# ESP32S3_DevBoard.net
KiCad netlist of a schematic drawn in EAGLE
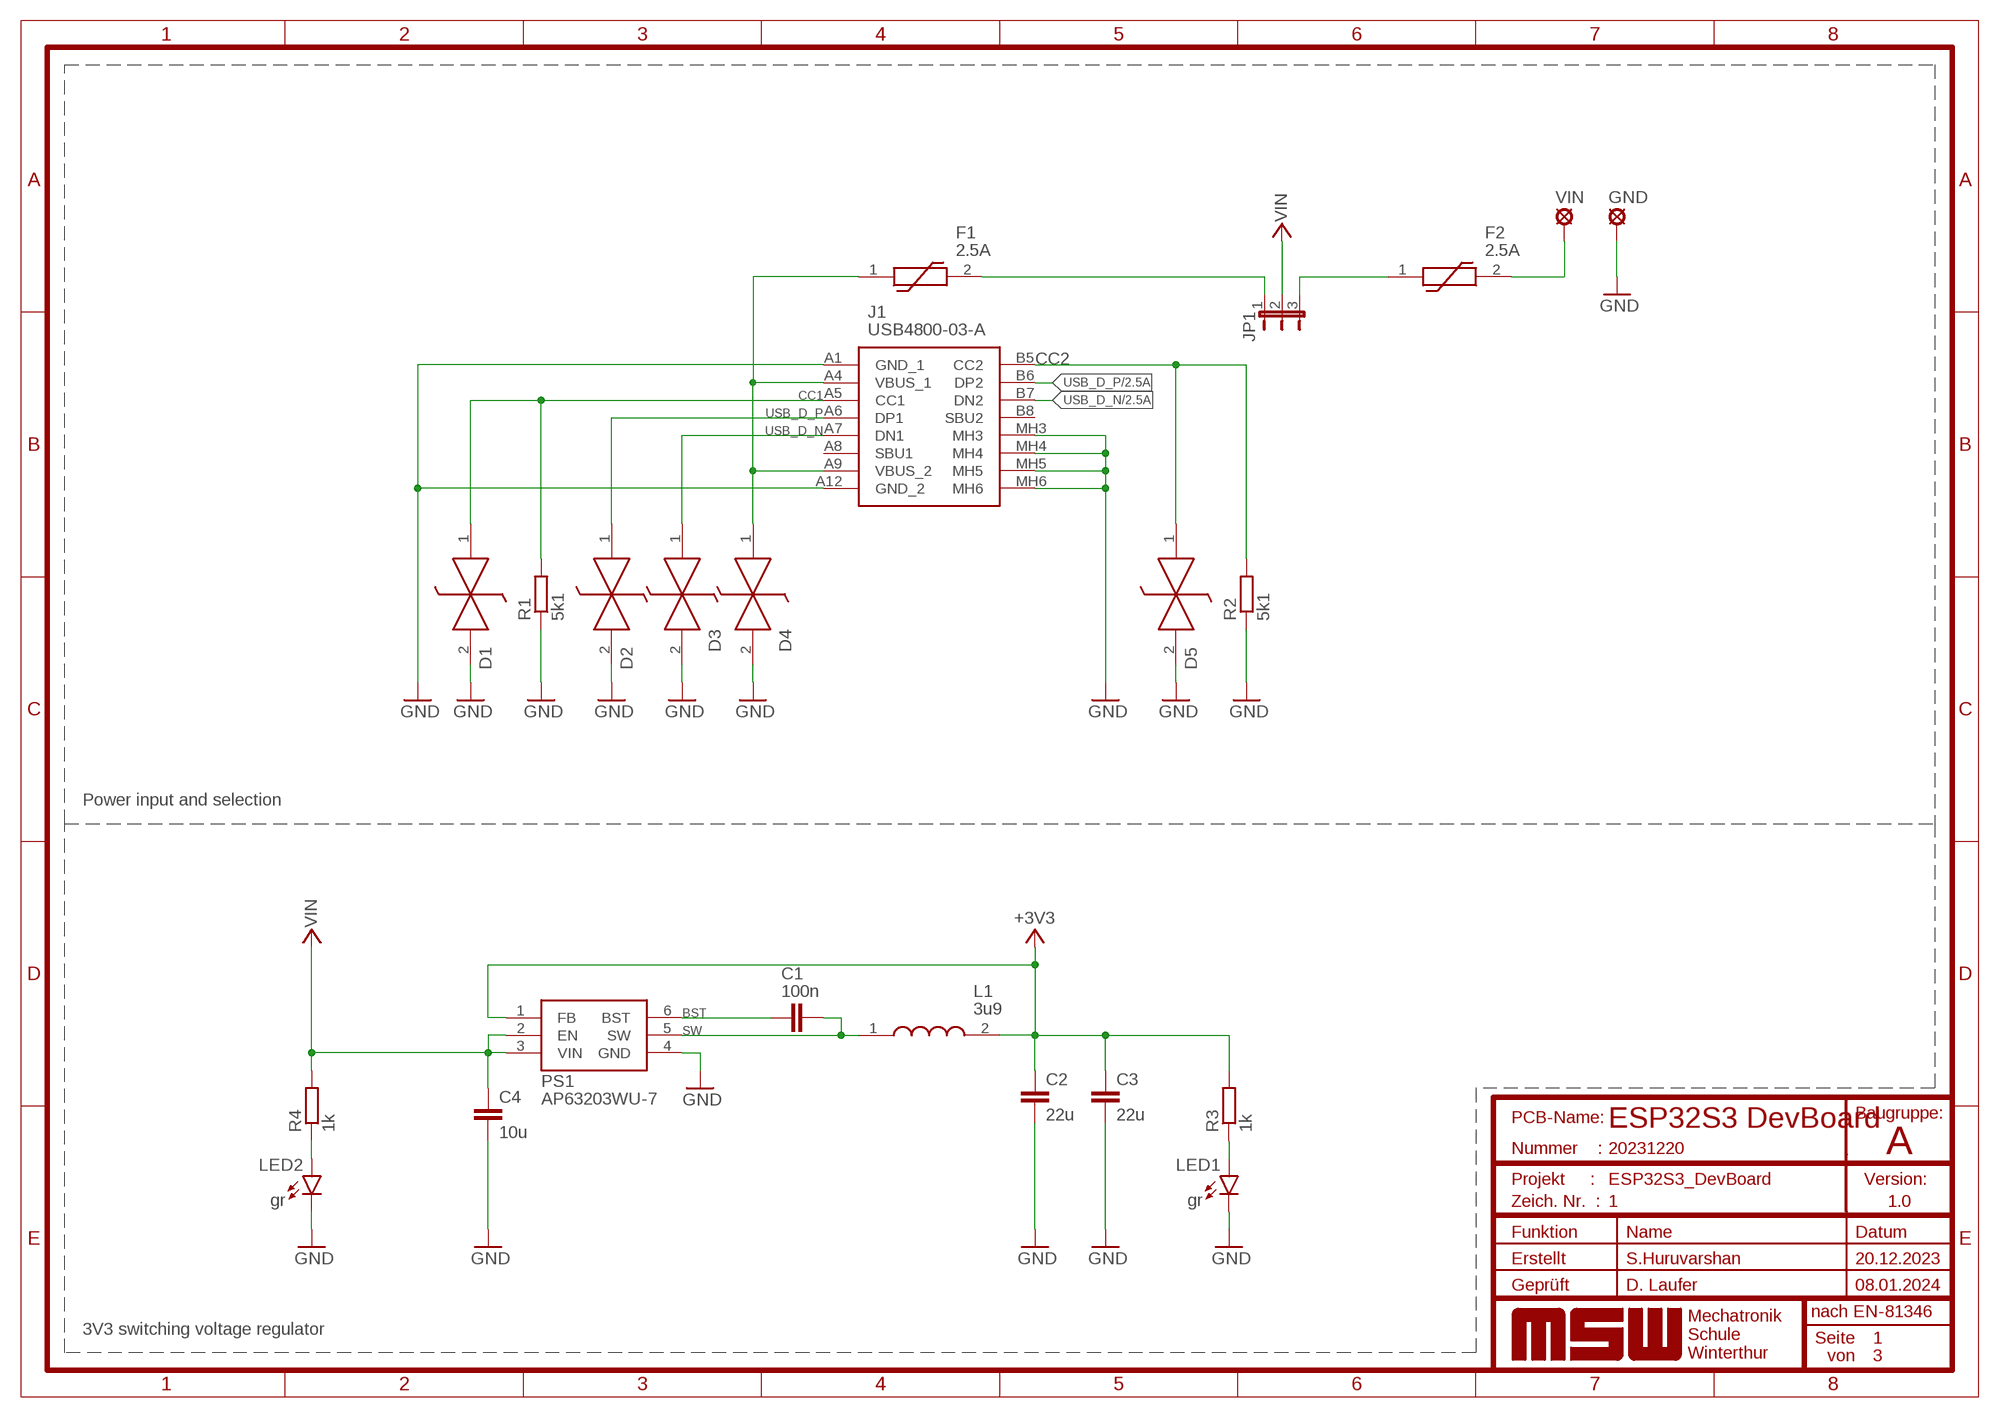
[diagram p0: schematic, sheet 1]
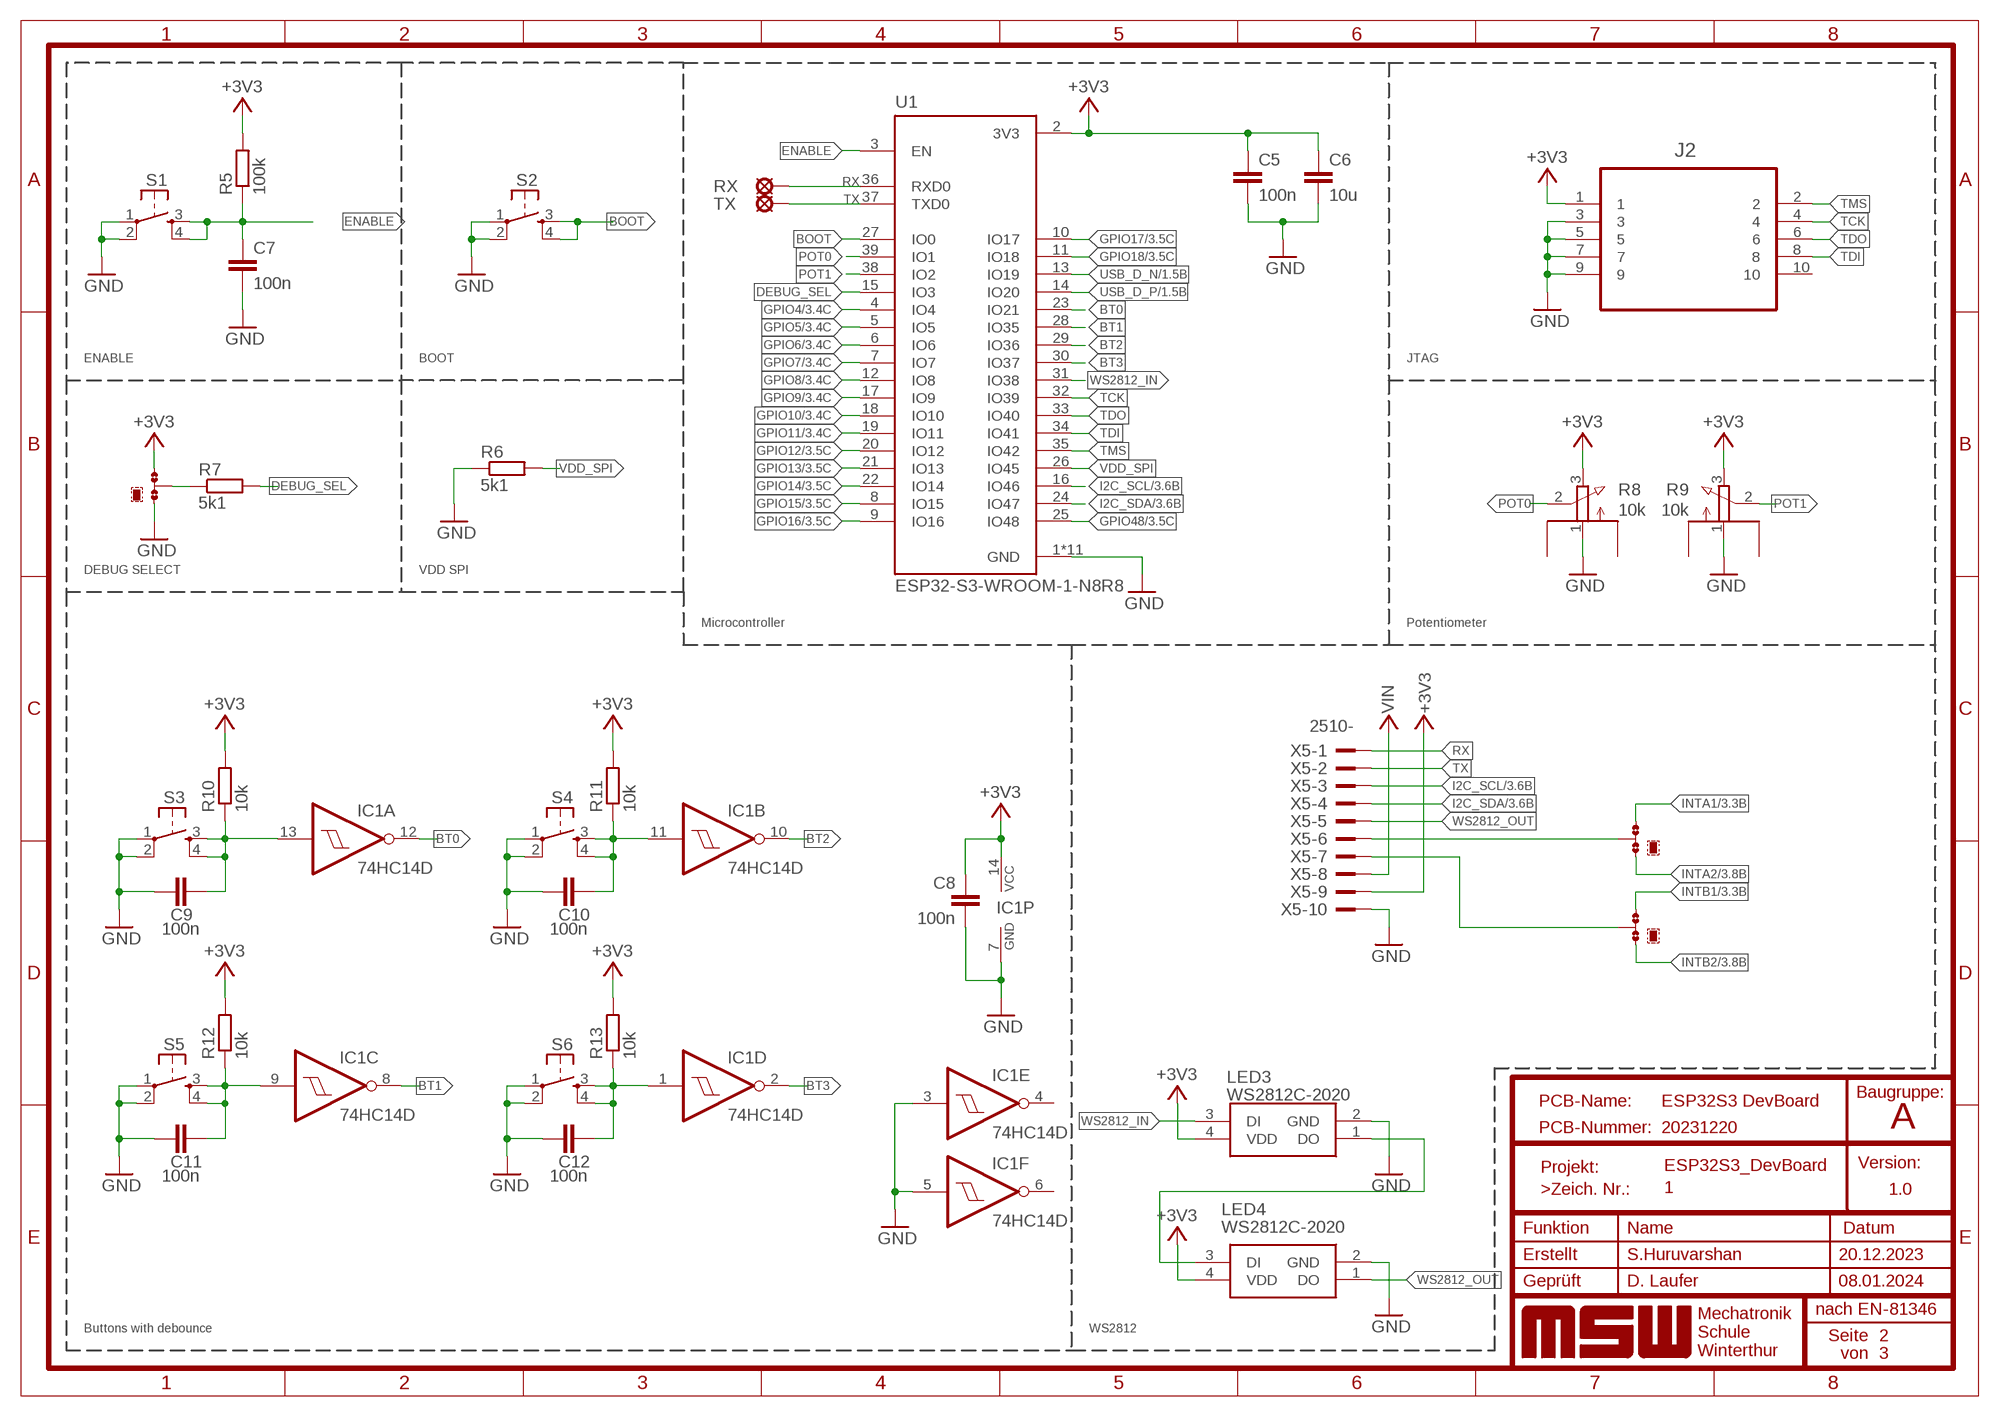
[diagram p1: schematic, sheet 2]
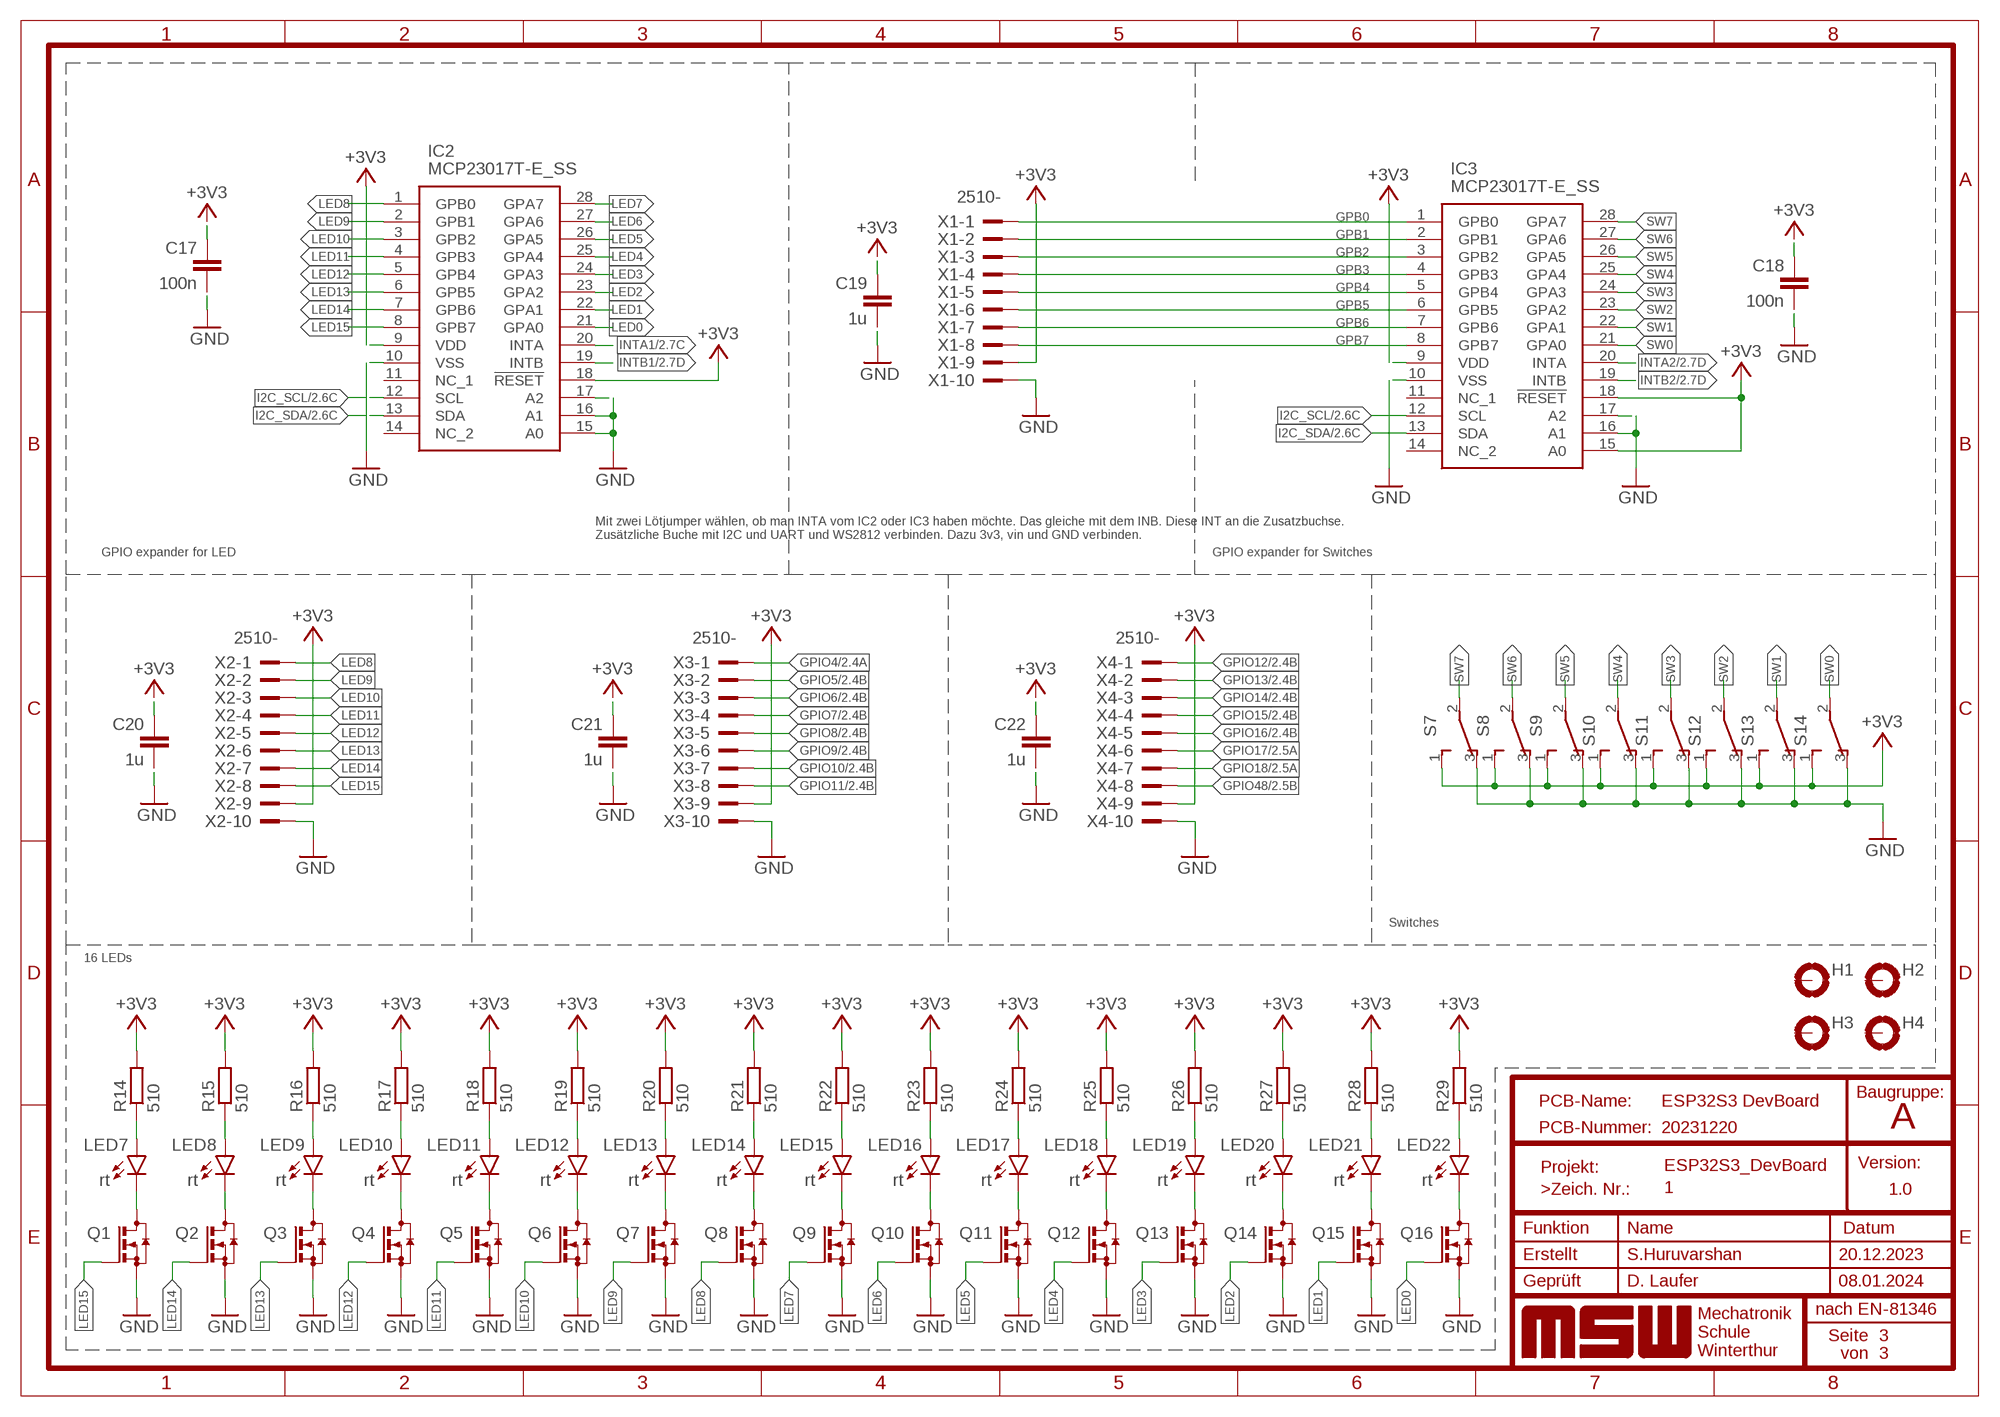
[diagram p2: schematic, sheet 3]

(export (version "E")
  (design (tool "Eeschema 10.0.6"))
  (components
    (comp (ref "C17")
      (value "100n")
      (footprint "eagle-import:C0805")
      (libsource (lib "eagle-import") (part "C-EUC0805"))
    )
    (comp (ref "C18")
      (value "100n")
      (footprint "eagle-import:C0805")
      (libsource (lib "eagle-import") (part "C-EUC0805"))
    )
    (comp (ref "C19")
      (value "1u")
      (footprint "eagle-import:C0805")
      (libsource (lib "eagle-import") (part "C-EUC0805"))
    )
    (comp (ref "C20")
      (value "1u")
      (footprint "eagle-import:C0805")
      (libsource (lib "eagle-import") (part "C-EUC0805"))
    )
    (comp (ref "C21")
      (value "1u")
      (footprint "eagle-import:C0805")
      (libsource (lib "eagle-import") (part "C-EUC0805"))
    )
    (comp (ref "C22")
      (value "1u")
      (footprint "eagle-import:C0805")
      (libsource (lib "eagle-import") (part "C-EUC0805"))
    )
    (comp (ref "H1")
      (value "MOUNT-PAD-ROUND3.3")
      (footprint "eagle-import:3,3-PAD")
      (libsource (lib "eagle-import") (part "MOUNT-PAD-ROUND3.3"))
    )
    (comp (ref "H2")
      (value "MOUNT-PAD-ROUND3.3")
      (footprint "eagle-import:3,3-PAD")
      (libsource (lib "eagle-import") (part "MOUNT-PAD-ROUND3.3"))
    )
    (comp (ref "H3")
      (value "MOUNT-PAD-ROUND3.3")
      (footprint "eagle-import:3,3-PAD")
      (libsource (lib "eagle-import") (part "MOUNT-PAD-ROUND3.3"))
    )
    (comp (ref "H4")
      (value "MOUNT-PAD-ROUND3.3")
      (footprint "eagle-import:3,3-PAD")
      (libsource (lib "eagle-import") (part "MOUNT-PAD-ROUND3.3"))
    )
    (comp (ref "IC2")
      (value "MCP23017T-E_SS")
      (footprint "eagle-import:SOP65P780X200-28N")
      (fields
        (field (name "MANUFACTURER_PART_NUMBER") "MCP23017T-E/SS")
        (field (name "MOUSER_PART_NUMBER") "579-MCP23017T-E/SS")
      )
      (libsource (lib "eagle-import") (part "MCP23017T-E_SS"))
    )
    (comp (ref "IC3")
      (value "MCP23017T-E_SS")
      (footprint "eagle-import:SOP65P780X200-28N")
      (fields
        (field (name "MANUFACTURER_PART_NUMBER") "MCP23017T-E/SS")
        (field (name "MOUSER_PART_NUMBER") "579-MCP23017T-E/SS")
      )
      (libsource (lib "eagle-import") (part "MCP23017T-E_SS"))
    )
    (comp (ref "LED7")
      (value "rt")
      (footprint "eagle-import:CHIPLED_1206")
      (libsource (lib "eagle-import") (part "LEDCHIPLED_1206"))
    )
    (comp (ref "LED8")
      (value "rt")
      (footprint "eagle-import:CHIPLED_1206")
      (libsource (lib "eagle-import") (part "LEDCHIPLED_1206"))
    )
    (comp (ref "LED9")
      (value "rt")
      (footprint "eagle-import:CHIPLED_1206")
      (libsource (lib "eagle-import") (part "LEDCHIPLED_1206"))
    )
    (comp (ref "LED10")
      (value "rt")
      (footprint "eagle-import:CHIPLED_1206")
      (libsource (lib "eagle-import") (part "LEDCHIPLED_1206"))
    )
    (comp (ref "LED11")
      (value "rt")
      (footprint "eagle-import:CHIPLED_1206")
      (libsource (lib "eagle-import") (part "LEDCHIPLED_1206"))
    )
    (comp (ref "LED12")
      (value "rt")
      (footprint "eagle-import:CHIPLED_1206")
      (libsource (lib "eagle-import") (part "LEDCHIPLED_1206"))
    )
    (comp (ref "LED13")
      (value "rt")
      (footprint "eagle-import:CHIPLED_1206")
      (libsource (lib "eagle-import") (part "LEDCHIPLED_1206"))
    )
    (comp (ref "LED14")
      (value "rt")
      (footprint "eagle-import:CHIPLED_1206")
      (libsource (lib "eagle-import") (part "LEDCHIPLED_1206"))
    )
    (comp (ref "LED15")
      (value "rt")
      (footprint "eagle-import:CHIPLED_1206")
      (libsource (lib "eagle-import") (part "LEDCHIPLED_1206"))
    )
    (comp (ref "LED16")
      (value "rt")
      (footprint "eagle-import:CHIPLED_1206")
      (libsource (lib "eagle-import") (part "LEDCHIPLED_1206"))
    )
    (comp (ref "LED17")
      (value "rt")
      (footprint "eagle-import:CHIPLED_1206")
      (libsource (lib "eagle-import") (part "LEDCHIPLED_1206"))
    )
    (comp (ref "LED18")
      (value "rt")
      (footprint "eagle-import:CHIPLED_1206")
      (libsource (lib "eagle-import") (part "LEDCHIPLED_1206"))
    )
    (comp (ref "LED19")
      (value "rt")
      (footprint "eagle-import:CHIPLED_1206")
      (libsource (lib "eagle-import") (part "LEDCHIPLED_1206"))
    )
    (comp (ref "LED20")
      (value "rt")
      (footprint "eagle-import:CHIPLED_1206")
      (libsource (lib "eagle-import") (part "LEDCHIPLED_1206"))
    )
    (comp (ref "LED21")
      (value "rt")
      (footprint "eagle-import:CHIPLED_1206")
      (libsource (lib "eagle-import") (part "LEDCHIPLED_1206"))
    )
    (comp (ref "LED22")
      (value "rt")
      (footprint "eagle-import:CHIPLED_1206")
      (libsource (lib "eagle-import") (part "LEDCHIPLED_1206"))
    )
    (comp (ref "Q1")
      (value "PMV20EN")
      (footprint "eagle-import:SOT23")
      (libsource (lib "eagle-import") (part "BSS123"))
    )
    (comp (ref "Q2")
      (value "PMV20EN")
      (footprint "eagle-import:SOT23")
      (libsource (lib "eagle-import") (part "BSS123"))
    )
    (comp (ref "Q3")
      (value "PMV20EN")
      (footprint "eagle-import:SOT23")
      (libsource (lib "eagle-import") (part "BSS123"))
    )
    (comp (ref "Q4")
      (value "PMV20EN")
      (footprint "eagle-import:SOT23")
      (libsource (lib "eagle-import") (part "BSS123"))
    )
    (comp (ref "Q5")
      (value "PMV20EN")
      (footprint "eagle-import:SOT23")
      (libsource (lib "eagle-import") (part "BSS123"))
    )
    (comp (ref "Q6")
      (value "PMV20EN")
      (footprint "eagle-import:SOT23")
      (libsource (lib "eagle-import") (part "BSS123"))
    )
    (comp (ref "Q7")
      (value "PMV20EN")
      (footprint "eagle-import:SOT23")
      (libsource (lib "eagle-import") (part "BSS123"))
    )
    (comp (ref "Q8")
      (value "PMV20EN")
      (footprint "eagle-import:SOT23")
      (libsource (lib "eagle-import") (part "BSS123"))
    )
    (comp (ref "Q9")
      (value "PMV20EN")
      (footprint "eagle-import:SOT23")
      (libsource (lib "eagle-import") (part "BSS123"))
    )
    (comp (ref "Q10")
      (value "PMV20EN")
      (footprint "eagle-import:SOT23")
      (libsource (lib "eagle-import") (part "BSS123"))
    )
    (comp (ref "Q11")
      (value "PMV20EN")
      (footprint "eagle-import:SOT23")
      (libsource (lib "eagle-import") (part "BSS123"))
    )
    (comp (ref "Q12")
      (value "PMV20EN")
      (footprint "eagle-import:SOT23")
      (libsource (lib "eagle-import") (part "BSS123"))
    )
    (comp (ref "Q13")
      (value "PMV20EN")
      (footprint "eagle-import:SOT23")
      (libsource (lib "eagle-import") (part "BSS123"))
    )
    (comp (ref "Q14")
      (value "PMV20EN")
      (footprint "eagle-import:SOT23")
      (libsource (lib "eagle-import") (part "BSS123"))
    )
    (comp (ref "Q15")
      (value "PMV20EN")
      (footprint "eagle-import:SOT23")
      (libsource (lib "eagle-import") (part "BSS123"))
    )
    (comp (ref "Q16")
      (value "PMV20EN")
      (footprint "eagle-import:SOT23")
      (libsource (lib "eagle-import") (part "BSS123"))
    )
    (comp (ref "R14")
      (value "510")
      (footprint "eagle-import:R0805")
      (libsource (lib "eagle-import") (part "R-EU_R0805"))
    )
    (comp (ref "R15")
      (value "510")
      (footprint "eagle-import:R0805")
      (libsource (lib "eagle-import") (part "R-EU_R0805"))
    )
    (comp (ref "R16")
      (value "510")
      (footprint "eagle-import:R0805")
      (libsource (lib "eagle-import") (part "R-EU_R0805"))
    )
    (comp (ref "R17")
      (value "510")
      (footprint "eagle-import:R0805")
      (libsource (lib "eagle-import") (part "R-EU_R0805"))
    )
    (comp (ref "R18")
      (value "510")
      (footprint "eagle-import:R0805")
      (libsource (lib "eagle-import") (part "R-EU_R0805"))
    )
    (comp (ref "R19")
      (value "510")
      (footprint "eagle-import:R0805")
      (libsource (lib "eagle-import") (part "R-EU_R0805"))
    )
    (comp (ref "R20")
      (value "510")
      (footprint "eagle-import:R0805")
      (libsource (lib "eagle-import") (part "R-EU_R0805"))
    )
    (comp (ref "R21")
      (value "510")
      (footprint "eagle-import:R0805")
      (libsource (lib "eagle-import") (part "R-EU_R0805"))
    )
    (comp (ref "R22")
      (value "510")
      (footprint "eagle-import:R0805")
      (libsource (lib "eagle-import") (part "R-EU_R0805"))
    )
    (comp (ref "R23")
      (value "510")
      (footprint "eagle-import:R0805")
      (libsource (lib "eagle-import") (part "R-EU_R0805"))
    )
    (comp (ref "R24")
      (value "510")
      (footprint "eagle-import:R0805")
      (libsource (lib "eagle-import") (part "R-EU_R0805"))
    )
    (comp (ref "R25")
      (value "510")
      (footprint "eagle-import:R0805")
      (libsource (lib "eagle-import") (part "R-EU_R0805"))
    )
    (comp (ref "R26")
      (value "510")
      (footprint "eagle-import:R0805")
      (libsource (lib "eagle-import") (part "R-EU_R0805"))
    )
    (comp (ref "R27")
      (value "510")
      (footprint "eagle-import:R0805")
      (libsource (lib "eagle-import") (part "R-EU_R0805"))
    )
    (comp (ref "R28")
      (value "510")
      (footprint "eagle-import:R0805")
      (libsource (lib "eagle-import") (part "R-EU_R0805"))
    )
    (comp (ref "R29")
      (value "510")
      (footprint "eagle-import:R0805")
      (libsource (lib "eagle-import") (part "R-EU_R0805"))
    )
    (comp (ref "S7")
      (value "TL36POSPDT_5MM")
      (footprint "eagle-import:SPDT_5MM")
      (libsource (lib "eagle-import") (part "TL36POSPDT_5MM"))
    )
    (comp (ref "S8")
      (value "TL36POSPDT_5MM")
      (footprint "eagle-import:SPDT_5MM")
      (libsource (lib "eagle-import") (part "TL36POSPDT_5MM"))
    )
    (comp (ref "S9")
      (value "TL36POSPDT_5MM")
      (footprint "eagle-import:SPDT_5MM")
      (libsource (lib "eagle-import") (part "TL36POSPDT_5MM"))
    )
    (comp (ref "S10")
      (value "TL36POSPDT_5MM")
      (footprint "eagle-import:SPDT_5MM")
      (libsource (lib "eagle-import") (part "TL36POSPDT_5MM"))
    )
    (comp (ref "S11")
      (value "TL36POSPDT_5MM")
      (footprint "eagle-import:SPDT_5MM")
      (libsource (lib "eagle-import") (part "TL36POSPDT_5MM"))
    )
    (comp (ref "S12")
      (value "TL36POSPDT_5MM")
      (footprint "eagle-import:SPDT_5MM")
      (libsource (lib "eagle-import") (part "TL36POSPDT_5MM"))
    )
    (comp (ref "S13")
      (value "TL36POSPDT_5MM")
      (footprint "eagle-import:SPDT_5MM")
      (libsource (lib "eagle-import") (part "TL36POSPDT_5MM"))
    )
    (comp (ref "S14")
      (value "TL36POSPDT_5MM")
      (footprint "eagle-import:SPDT_5MM")
      (libsource (lib "eagle-import") (part "TL36POSPDT_5MM"))
    )
    (comp (ref "X1")
      (value "2510-")
      (footprint "eagle-import:PAK100_2500-10")
      (fields (field (name "MF") "3M") (field (name "MPN") "2510-6002UB"))
      (libsource (lib "eagle-import") (part "2510-"))
    )
    (comp (ref "X2")
      (value "2510-")
      (footprint "eagle-import:PAK100_2500-10")
      (fields (field (name "MF") "3M") (field (name "MPN") "2510-6002UB"))
      (libsource (lib "eagle-import") (part "2510-"))
    )
    (comp (ref "X3")
      (value "2510-")
      (footprint "eagle-import:PAK100_2500-10")
      (fields (field (name "MF") "3M") (field (name "MPN") "2510-6002UB"))
      (libsource (lib "eagle-import") (part "2510-"))
    )
    (comp (ref "X4")
      (value "2510-")
      (footprint "eagle-import:PAK100_2500-10")
      (fields (field (name "MF") "3M") (field (name "MPN") "2510-6002UB"))
      (libsource (lib "eagle-import") (part "2510-"))
    )
    (comp (ref "C1")
      (value "100n")
      (footprint "eagle-import:C0805")
      (libsource (lib "eagle-import") (part "C-EUC0805"))
    )
    (comp (ref "C2")
      (value "22u")
      (footprint "eagle-import:C1206")
      (libsource (lib "eagle-import") (part "C-EUC1206"))
    )
    (comp (ref "C3")
      (value "22u")
      (footprint "eagle-import:C1206")
      (libsource (lib "eagle-import") (part "C-EUC1206"))
    )
    (comp (ref "C4")
      (value "10u")
      (footprint "eagle-import:C1206")
      (libsource (lib "eagle-import") (part "C-EUC1206"))
    )
    (comp (ref "D1")
      (value "GG060305100N2P")
      (footprint "eagle-import:DIONC1608X70N")
      (fields (field (name "MOUSER_PART_NUMBER") "581-GG060305100N2P"))
      (libsource (lib "eagle-import") (part "GG060305100N2P"))
    )
    (comp (ref "D2")
      (value "GG060305100N2P")
      (footprint "eagle-import:DIONC1608X70N")
      (fields (field (name "MOUSER_PART_NUMBER") "581-GG060305100N2P"))
      (libsource (lib "eagle-import") (part "GG060305100N2P"))
    )
    (comp (ref "D3")
      (value "GG060305100N2P")
      (footprint "eagle-import:DIONC1608X70N")
      (fields (field (name "MOUSER_PART_NUMBER") "581-GG060305100N2P"))
      (libsource (lib "eagle-import") (part "GG060305100N2P"))
    )
    (comp (ref "D4")
      (value "GG060305100N2P")
      (footprint "eagle-import:DIONC1608X70N")
      (fields (field (name "MOUSER_PART_NUMBER") "581-GG060305100N2P"))
      (libsource (lib "eagle-import") (part "GG060305100N2P"))
    )
    (comp (ref "D5")
      (value "GG060305100N2P")
      (footprint "eagle-import:DIONC1608X70N")
      (fields (field (name "MOUSER_PART_NUMBER") "581-GG060305100N2P"))
      (libsource (lib "eagle-import") (part "GG060305100N2P"))
    )
    (comp (ref "F1")
      (value "2.5A")
      (footprint "eagle-import:2920L030DR")
      (fields
        (field (name "MANUFACTURER_PART_NUMBER") "2920L250DR")
        (field (name "MOUSER_PART_NUMBER") "576-2920L250")
      )
      (libsource (lib "eagle-import") (part "2920L250DR"))
    )
    (comp (ref "F2")
      (value "2.5A")
      (footprint "eagle-import:2920L030DR")
      (fields
        (field (name "MANUFACTURER_PART_NUMBER") "2920L250DR")
        (field (name "MOUSER_PART_NUMBER") "576-2920L250")
      )
      (libsource (lib "eagle-import") (part "2920L250DR"))
    )
    (comp (ref "GND")
      (value "LSP10")
      (footprint "eagle-import:LSP10")
      (libsource (lib "eagle-import") (part "LSP10"))
    )
    (comp (ref "J1")
      (value "USB4800-03-A")
      (footprint "eagle-import:USB480003A")
      (fields (field (name "MOUSER_PART_NUMBER") "640-USB4800-03-A"))
      (libsource (lib "eagle-import") (part "USB4800-03-A"))
    )
    (comp (ref "JP1")
      (value "JP2W")
      (footprint "eagle-import:JP2W")
      (libsource (lib "eagle-import") (part "JP2W"))
    )
    (comp (ref "L1")
      (value "3u9")
      (footprint "eagle-import:74404052039")
      (fields
        (field (name "MANUFACTURER_PART_NUMBER") "74404052039")
        (field (name "MOUSER_PART_NUMBER") "710-74404052039")
      )
      (libsource (lib "eagle-import") (part "74404052039"))
    )
    (comp (ref "LED1")
      (value "gr")
      (footprint "eagle-import:CHIPLED_1206")
      (libsource (lib "eagle-import") (part "LEDCHIPLED_1206"))
    )
    (comp (ref "LED2")
      (value "gr")
      (footprint "eagle-import:CHIPLED_1206")
      (libsource (lib "eagle-import") (part "LEDCHIPLED_1206"))
    )
    (comp (ref "PS1")
      (value "AP63203WU-7")
      (footprint "eagle-import:SOT95P280X100-6N")
      (fields (field (name "MOUSER_PART_NUMBER") "621-AP63203WU-7"))
      (libsource (lib "eagle-import") (part "AP63203WU-7"))
    )
    (comp (ref "R1")
      (value "5k1")
      (footprint "eagle-import:R0805")
      (libsource (lib "eagle-import") (part "R-EU_R0805"))
    )
    (comp (ref "R2")
      (value "5k1")
      (footprint "eagle-import:R0805")
      (libsource (lib "eagle-import") (part "R-EU_R0805"))
    )
    (comp (ref "R3")
      (value "1k")
      (footprint "eagle-import:R0805")
      (libsource (lib "eagle-import") (part "R-EU_R0805"))
    )
    (comp (ref "R4")
      (value "1k")
      (footprint "eagle-import:R0805")
      (libsource (lib "eagle-import") (part "R-EU_R0805"))
    )
    (comp (ref "VIN")
      (value "LSP10")
      (footprint "eagle-import:LSP10")
      (libsource (lib "eagle-import") (part "LSP10"))
    )
    (comp (ref "C5")
      (value "100n")
      (footprint "eagle-import:C0805")
      (libsource (lib "eagle-import") (part "C-EUC0805"))
    )
    (comp (ref "C6")
      (value "10u")
      (footprint "eagle-import:C1206")
      (libsource (lib "eagle-import") (part "C-EUC1206"))
    )
    (comp (ref "C7")
      (value "100n")
      (footprint "eagle-import:C0805")
      (libsource (lib "eagle-import") (part "C-EUC0805"))
    )
    (comp (ref "C8")
      (value "100n")
      (footprint "eagle-import:C0805")
      (libsource (lib "eagle-import") (part "C-EUC0805"))
    )
    (comp (ref "C9")
      (value "100n")
      (footprint "eagle-import:C0805")
      (libsource (lib "eagle-import") (part "C-EUC0805"))
    )
    (comp (ref "C10")
      (value "100n")
      (footprint "eagle-import:C0805")
      (libsource (lib "eagle-import") (part "C-EUC0805"))
    )
    (comp (ref "C11")
      (value "100n")
      (footprint "eagle-import:C0805")
      (libsource (lib "eagle-import") (part "C-EUC0805"))
    )
    (comp (ref "C12")
      (value "100n")
      (footprint "eagle-import:C0805")
      (libsource (lib "eagle-import") (part "C-EUC0805"))
    )
    (comp (ref "IC1")
      (value "74HC14D")
      (footprint "eagle-import:SO14")
      (libsource (lib "eagle-import") (part "7414DHC"))
    )
    (comp (ref "J2")
      (value "3220-10-0100-00")
      (footprint "eagle-import:SAMTEC_FTS-105-01-L-D")
      (fields (field (name "MPN") "FTS-105-01-L-D"))
      (libsource (lib "eagle-import") (part "FTS-105-01-L-D"))
    )
    (comp (ref "JMP1")
      (value "0R-JUMPC")
      (footprint "eagle-import:C0R-JMP")
      (libsource (lib "eagle-import") (part "0R-JUMPC"))
    )
    (comp (ref "JMP2")
      (value "0R-JUMPC")
      (footprint "eagle-import:C0R-JMP")
      (libsource (lib "eagle-import") (part "0R-JUMPC"))
    )
    (comp (ref "JMP3")
      (value "0R-JUMPC")
      (footprint "eagle-import:C0R-JMP")
      (libsource (lib "eagle-import") (part "0R-JUMPC"))
    )
    (comp (ref "LED3")
      (value "WS2812C-2020")
      (footprint "eagle-import:WS2812C2020")
      (libsource (lib "eagle-import") (part "WS2812C-2020"))
    )
    (comp (ref "LED4")
      (value "WS2812C-2020")
      (footprint "eagle-import:WS2812C2020")
      (libsource (lib "eagle-import") (part "WS2812C-2020"))
    )
    (comp (ref "R5")
      (value "100k")
      (footprint "eagle-import:R0805")
      (libsource (lib "eagle-import") (part "R-EU_R0805"))
    )
    (comp (ref "R6")
      (value "5k1")
      (footprint "eagle-import:R0805")
      (libsource (lib "eagle-import") (part "R-EU_R0805"))
    )
    (comp (ref "R7")
      (value "5k1")
      (footprint "eagle-import:R0805")
      (libsource (lib "eagle-import") (part "R-EU_R0805"))
    )
    (comp (ref "R8")
      (value "10k")
      (footprint "eagle-import:EVUF")
      (libsource (lib "eagle-import") (part "EVUA"))
    )
    (comp (ref "R9")
      (value "10k")
      (footprint "eagle-import:EVUF")
      (libsource (lib "eagle-import") (part "EVUA"))
    )
    (comp (ref "R10")
      (value "10k")
      (footprint "eagle-import:R0805")
      (libsource (lib "eagle-import") (part "R-EU_R0805"))
    )
    (comp (ref "R11")
      (value "10k")
      (footprint "eagle-import:R0805")
      (libsource (lib "eagle-import") (part "R-EU_R0805"))
    )
    (comp (ref "R12")
      (value "10k")
      (footprint "eagle-import:R0805")
      (libsource (lib "eagle-import") (part "R-EU_R0805"))
    )
    (comp (ref "R13")
      (value "10k")
      (footprint "eagle-import:R0805")
      (libsource (lib "eagle-import") (part "R-EU_R0805"))
    )
    (comp (ref "RX")
      (value "LSP10")
      (footprint "eagle-import:LSP10")
      (libsource (lib "eagle-import") (part "LSP10"))
    )
    (comp (ref "S1")
      (value "TS42_4PAD")
      (footprint "eagle-import:TS42_4PAD")
      (libsource (lib "eagle-import") (part "TS42_4PAD"))
    )
    (comp (ref "S2")
      (value "TS42_4PAD")
      (footprint "eagle-import:TS42_4PAD")
      (libsource (lib "eagle-import") (part "TS42_4PAD"))
    )
    (comp (ref "S3")
      (value "TS42_4PAD")
      (footprint "eagle-import:TS42_4PAD")
      (libsource (lib "eagle-import") (part "TS42_4PAD"))
    )
    (comp (ref "S4")
      (value "TS42_4PAD")
      (footprint "eagle-import:TS42_4PAD")
      (libsource (lib "eagle-import") (part "TS42_4PAD"))
    )
    (comp (ref "S5")
      (value "TS42_4PAD")
      (footprint "eagle-import:TS42_4PAD")
      (libsource (lib "eagle-import") (part "TS42_4PAD"))
    )
    (comp (ref "S6")
      (value "TS42_4PAD")
      (footprint "eagle-import:TS42_4PAD")
      (libsource (lib "eagle-import") (part "TS42_4PAD"))
    )
    (comp (ref "TX")
      (value "LSP10")
      (footprint "eagle-import:LSP10")
      (libsource (lib "eagle-import") (part "LSP10"))
    )
    (comp (ref "U1")
      (value "ESP32-S3-WROOM-1-N8R8")
      (footprint "eagle-import:XCVR_ESP32S3WROOM1N8R8")
      (fields (field (name "MF") "Espressif Systems"))
      (libsource (lib "eagle-import") (part "ESP32-S3-WROOM-1-N8R8"))
    )
    (comp (ref "X5")
      (value "2510-")
      (footprint "eagle-import:PAK100_2500-10")
      (fields (field (name "MF") "3M") (field (name "MPN") "2510-6002UB"))
      (libsource (lib "eagle-import") (part "2510-"))
    )
  )
  (nets
    (net (code "1") (name "+3V3") (class "Default")
      (node (ref "C17") (pin "1") (pinfunction "1_1") (pintype "passive"))
      (node (ref "C18") (pin "1") (pinfunction "1_1") (pintype "passive"))
      (node (ref "C19") (pin "1") (pinfunction "1_1") (pintype "passive"))
      (node (ref "C2") (pin "1") (pinfunction "1_1") (pintype "passive"))
      (node (ref "C20") (pin "1") (pinfunction "1_1") (pintype "passive"))
      (node (ref "C21") (pin "1") (pinfunction "1_1") (pintype "passive"))
      (node (ref "C22") (pin "1") (pinfunction "1_1") (pintype "passive"))
      (node (ref "C3") (pin "1") (pinfunction "1_1") (pintype "passive"))
      (node (ref "C5") (pin "1") (pinfunction "1_1") (pintype "passive"))
      (node (ref "C6") (pin "1") (pinfunction "1_1") (pintype "passive"))
      (node (ref "C8") (pin "1") (pinfunction "1_1") (pintype "passive"))
      (node (ref "IC1") (pin "14") (pinfunction "VCC_14") (pintype "power_in"))
      (node (ref "IC2") (pin "18") (pinfunction "~{RESET}_18") (pintype "bidirectional"))
      (node (ref "IC2") (pin "9") (pinfunction "VDD_9") (pintype "bidirectional"))
      (node (ref "IC3") (pin "15") (pinfunction "A0_15") (pintype "bidirectional"))
      (node (ref "IC3") (pin "18") (pinfunction "~{RESET}_18") (pintype "bidirectional"))
      (node (ref "IC3") (pin "9") (pinfunction "VDD_9") (pintype "bidirectional"))
      (node (ref "J2") (pin "1") (pinfunction "1_1") (pintype "passive"))
      (node (ref "JMP1") (pin "1") (pinfunction "1_1") (pintype "passive"))
      (node (ref "L1") (pin "2") (pinfunction "2_2") (pintype "bidirectional"))
      (node (ref "LED3") (pin "4") (pinfunction "VDD_4") (pintype "bidirectional"))
      (node (ref "LED4") (pin "4") (pinfunction "VDD_4") (pintype "bidirectional"))
      (node (ref "PS1") (pin "1") (pinfunction "FB_1") (pintype "input"))
      (node (ref "R10") (pin "2") (pinfunction "2_2") (pintype "passive"))
      (node (ref "R11") (pin "2") (pinfunction "2_2") (pintype "passive"))
      (node (ref "R12") (pin "2") (pinfunction "2_2") (pintype "passive"))
      (node (ref "R13") (pin "2") (pinfunction "2_2") (pintype "passive"))
      (node (ref "R14") (pin "2") (pinfunction "2_2") (pintype "passive"))
      (node (ref "R15") (pin "2") (pinfunction "2_2") (pintype "passive"))
      (node (ref "R16") (pin "2") (pinfunction "2_2") (pintype "passive"))
      (node (ref "R17") (pin "2") (pinfunction "2_2") (pintype "passive"))
      (node (ref "R18") (pin "2") (pinfunction "2_2") (pintype "passive"))
      (node (ref "R19") (pin "2") (pinfunction "2_2") (pintype "passive"))
      (node (ref "R20") (pin "2") (pinfunction "2_2") (pintype "passive"))
      (node (ref "R21") (pin "2") (pinfunction "2_2") (pintype "passive"))
      (node (ref "R22") (pin "2") (pinfunction "2_2") (pintype "passive"))
      (node (ref "R23") (pin "2") (pinfunction "2_2") (pintype "passive"))
      (node (ref "R24") (pin "2") (pinfunction "2_2") (pintype "passive"))
      (node (ref "R25") (pin "2") (pinfunction "2_2") (pintype "passive"))
      (node (ref "R26") (pin "2") (pinfunction "2_2") (pintype "passive"))
      (node (ref "R27") (pin "2") (pinfunction "2_2") (pintype "passive"))
      (node (ref "R28") (pin "2") (pinfunction "2_2") (pintype "passive"))
      (node (ref "R29") (pin "2") (pinfunction "2_2") (pintype "passive"))
      (node (ref "R3") (pin "2") (pinfunction "2_2") (pintype "passive"))
      (node (ref "R5") (pin "2") (pinfunction "2_2") (pintype "passive"))
      (node (ref "R8") (pin "3") (pinfunction "E_3") (pintype "passive"))
      (node (ref "R9") (pin "3") (pinfunction "E_3") (pintype "passive"))
      (node (ref "S10") (pin "1") (pinfunction "S_1") (pintype "passive"))
      (node (ref "S11") (pin "1") (pinfunction "S_1") (pintype "passive"))
      (node (ref "S12") (pin "1") (pinfunction "S_1") (pintype "passive"))
      (node (ref "S13") (pin "1") (pinfunction "S_1") (pintype "passive"))
      (node (ref "S14") (pin "1") (pinfunction "S_1") (pintype "passive"))
      (node (ref "S7") (pin "1") (pinfunction "S_1") (pintype "passive"))
      (node (ref "S8") (pin "1") (pinfunction "S_1") (pintype "passive"))
      (node (ref "S9") (pin "1") (pinfunction "S_1") (pintype "passive"))
      (node (ref "U1") (pin "2") (pinfunction "3V3_2") (pintype "power_in"))
      (node (ref "X1") (pin "9") (pinfunction "KL_9") (pintype "passive"))
      (node (ref "X2") (pin "9") (pinfunction "KL_9") (pintype "passive"))
      (node (ref "X3") (pin "9") (pinfunction "KL_9") (pintype "passive"))
      (node (ref "X4") (pin "9") (pinfunction "KL_9") (pintype "passive"))
      (node (ref "X5") (pin "9") (pinfunction "KL_9") (pintype "passive"))
    )
    (net (code "2") (name "BOOT") (class "Default")
      (node (ref "S2") (pin "3") (pinfunction "3_3") (pintype "passive"))
      (node (ref "S2") (pin "4") (pinfunction "4_4") (pintype "passive"))
      (node (ref "U1") (pin "27") (pinfunction "IO0_27") (pintype "bidirectional"))
    )
    (net (code "3") (name "BST") (class "Default")
      (node (ref "C1") (pin "1") (pinfunction "1_1") (pintype "passive"))
      (node (ref "PS1") (pin "6") (pinfunction "BST_6") (pintype "input"))
    )
    (net (code "4") (name "BT0") (class "Default")
      (node (ref "IC1") (pin "12") (pinfunction "O_12") (pintype "output"))
      (node (ref "U1") (pin "23") (pinfunction "IO21_23") (pintype "bidirectional"))
    )
    (net (code "5") (name "BT1") (class "Default")
      (node (ref "IC1") (pin "8") (pinfunction "O_8") (pintype "output"))
      (node (ref "U1") (pin "28") (pinfunction "IO35_28") (pintype "bidirectional"))
    )
    (net (code "6") (name "BT2") (class "Default")
      (node (ref "IC1") (pin "10") (pinfunction "O_10") (pintype "output"))
      (node (ref "U1") (pin "29") (pinfunction "IO36_29") (pintype "bidirectional"))
    )
    (net (code "7") (name "BT3") (class "Default")
      (node (ref "IC1") (pin "2") (pinfunction "O_2") (pintype "output"))
      (node (ref "U1") (pin "30") (pinfunction "IO37_30") (pintype "bidirectional"))
    )
    (net (code "8") (name "CC1") (class "Default")
      (node (ref "D1") (pin "1") (pinfunction "K1_1") (pintype "bidirectional"))
      (node (ref "J1") (pin "A5") (pinfunction "CC1_A5") (pintype "bidirectional"))
      (node (ref "R1") (pin "2") (pinfunction "2_2") (pintype "passive"))
    )
    (net (code "9") (name "CC2") (class "Default")
      (node (ref "D5") (pin "1") (pinfunction "K1_1") (pintype "bidirectional"))
      (node (ref "J1") (pin "B5") (pinfunction "CC2_B5") (pintype "bidirectional"))
      (node (ref "R2") (pin "2") (pinfunction "2_2") (pintype "passive"))
    )
    (net (code "10") (name "DEBUG_SEL") (class "Default")
      (node (ref "R7") (pin "2") (pinfunction "2_2") (pintype "passive"))
      (node (ref "U1") (pin "15") (pinfunction "IO3_15") (pintype "bidirectional"))
    )
    (net (code "11") (name "ENABLE") (class "Default")
      (node (ref "C7") (pin "1") (pinfunction "1_1") (pintype "passive"))
      (node (ref "R5") (pin "1") (pinfunction "1_1") (pintype "passive"))
      (node (ref "S1") (pin "3") (pinfunction "3_3") (pintype "passive"))
      (node (ref "S1") (pin "4") (pinfunction "4_4") (pintype "passive"))
      (node (ref "U1") (pin "3") (pinfunction "EN_3") (pintype "input"))
    )
    (net (code "12") (name "GND") (class "Default")
      (node (ref "C10") (pin "2") (pinfunction "2_2") (pintype "passive"))
      (node (ref "C11") (pin "2") (pinfunction "2_2") (pintype "passive"))
      (node (ref "C12") (pin "2") (pinfunction "2_2") (pintype "passive"))
      (node (ref "C17") (pin "2") (pinfunction "2_2") (pintype "passive"))
      (node (ref "C18") (pin "2") (pinfunction "2_2") (pintype "passive"))
      (node (ref "C19") (pin "2") (pinfunction "2_2") (pintype "passive"))
      (node (ref "C2") (pin "2") (pinfunction "2_2") (pintype "passive"))
      (node (ref "C20") (pin "2") (pinfunction "2_2") (pintype "passive"))
      (node (ref "C21") (pin "2") (pinfunction "2_2") (pintype "passive"))
      (node (ref "C22") (pin "2") (pinfunction "2_2") (pintype "passive"))
      (node (ref "C3") (pin "2") (pinfunction "2_2") (pintype "passive"))
      (node (ref "C4") (pin "2") (pinfunction "2_2") (pintype "passive"))
      (node (ref "C5") (pin "2") (pinfunction "2_2") (pintype "passive"))
      (node (ref "C6") (pin "2") (pinfunction "2_2") (pintype "passive"))
      (node (ref "C7") (pin "2") (pinfunction "2_2") (pintype "passive"))
      (node (ref "C8") (pin "2") (pinfunction "2_2") (pintype "passive"))
      (node (ref "C9") (pin "2") (pinfunction "2_2") (pintype "passive"))
      (node (ref "D1") (pin "2") (pinfunction "K2_2") (pintype "bidirectional"))
      (node (ref "D2") (pin "2") (pinfunction "K2_2") (pintype "bidirectional"))
      (node (ref "D3") (pin "2") (pinfunction "K2_2") (pintype "bidirectional"))
      (node (ref "D4") (pin "2") (pinfunction "K2_2") (pintype "bidirectional"))
      (node (ref "D5") (pin "2") (pinfunction "K2_2") (pintype "bidirectional"))
      (node (ref "GND") (pin "MP") (pinfunction "MP_MP") (pintype "passive"))
      (node (ref "IC1") (pin "3") (pinfunction "I_3") (pintype "input"))
      (node (ref "IC1") (pin "5") (pinfunction "I_5") (pintype "input"))
      (node (ref "IC1") (pin "7") (pinfunction "GND_7") (pintype "power_in"))
      (node (ref "IC2") (pin "10") (pinfunction "VSS_10") (pintype "bidirectional"))
      (node (ref "IC2") (pin "15") (pinfunction "A0_15") (pintype "bidirectional"))
      (node (ref "IC2") (pin "16") (pinfunction "A1_16") (pintype "bidirectional"))
      (node (ref "IC2") (pin "17") (pinfunction "A2_17") (pintype "bidirectional"))
      (node (ref "IC3") (pin "10") (pinfunction "VSS_10") (pintype "bidirectional"))
      (node (ref "IC3") (pin "16") (pinfunction "A1_16") (pintype "bidirectional"))
      (node (ref "IC3") (pin "17") (pinfunction "A2_17") (pintype "bidirectional"))
      (node (ref "J1") (pin "A1") (pinfunction "GND_1_A1") (pintype "bidirectional"))
      (node (ref "J1") (pin "A12") (pinfunction "GND_2_A12") (pintype "bidirectional"))
      (node (ref "J1") (pin "MH3") (pinfunction "MH3_MH3") (pintype "bidirectional"))
      (node (ref "J1") (pin "MH4") (pinfunction "MH4_MH4") (pintype "bidirectional"))
      (node (ref "J1") (pin "MH5") (pinfunction "MH5_MH5") (pintype "bidirectional"))
      (node (ref "J1") (pin "MH6") (pinfunction "MH6_MH6") (pintype "bidirectional"))
      (node (ref "J2") (pin "3") (pinfunction "3_3") (pintype "passive"))
      (node (ref "J2") (pin "5") (pinfunction "5_5") (pintype "passive"))
      (node (ref "J2") (pin "7") (pinfunction "7_7") (pintype "passive"))
      (node (ref "J2") (pin "9") (pinfunction "9_9") (pintype "passive"))
      (node (ref "JMP1") (pin "3") (pinfunction "3_3") (pintype "passive"))
      (node (ref "LED1") (pin "C") (pinfunction "C_C") (pintype "passive"))
      (node (ref "LED2") (pin "C") (pinfunction "C_C") (pintype "passive"))
      (node (ref "LED3") (pin "2") (pinfunction "GND_2") (pintype "bidirectional"))
      (node (ref "LED4") (pin "2") (pinfunction "GND_2") (pintype "bidirectional"))
      (node (ref "PS1") (pin "4") (pinfunction "GND_4") (pintype "power_in"))
      (node (ref "Q1") (pin "2") (pinfunction "S_2") (pintype "passive"))
      (node (ref "Q10") (pin "2") (pinfunction "S_2") (pintype "passive"))
      (node (ref "Q11") (pin "2") (pinfunction "S_2") (pintype "passive"))
      (node (ref "Q12") (pin "2") (pinfunction "S_2") (pintype "passive"))
      (node (ref "Q13") (pin "2") (pinfunction "S_2") (pintype "passive"))
      (node (ref "Q14") (pin "2") (pinfunction "S_2") (pintype "passive"))
      (node (ref "Q15") (pin "2") (pinfunction "S_2") (pintype "passive"))
      (node (ref "Q16") (pin "2") (pinfunction "S_2") (pintype "passive"))
      (node (ref "Q2") (pin "2") (pinfunction "S_2") (pintype "passive"))
      (node (ref "Q3") (pin "2") (pinfunction "S_2") (pintype "passive"))
      (node (ref "Q4") (pin "2") (pinfunction "S_2") (pintype "passive"))
      (node (ref "Q5") (pin "2") (pinfunction "S_2") (pintype "passive"))
      (node (ref "Q6") (pin "2") (pinfunction "S_2") (pintype "passive"))
      (node (ref "Q7") (pin "2") (pinfunction "S_2") (pintype "passive"))
      (node (ref "Q8") (pin "2") (pinfunction "S_2") (pintype "passive"))
      (node (ref "Q9") (pin "2") (pinfunction "S_2") (pintype "passive"))
      (node (ref "R1") (pin "1") (pinfunction "1_1") (pintype "passive"))
      (node (ref "R2") (pin "1") (pinfunction "1_1") (pintype "passive"))
      (node (ref "R6") (pin "1") (pinfunction "1_1") (pintype "passive"))
      (node (ref "R8") (pin "1") (pinfunction "A_1") (pintype "passive"))
      (node (ref "R9") (pin "1") (pinfunction "A_1") (pintype "passive"))
      (node (ref "S1") (pin "1") (pinfunction "1_1") (pintype "passive"))
      (node (ref "S1") (pin "2") (pinfunction "2_2") (pintype "passive"))
      (node (ref "S10") (pin "3") (pinfunction "O_3") (pintype "passive"))
      (node (ref "S11") (pin "3") (pinfunction "O_3") (pintype "passive"))
      (node (ref "S12") (pin "3") (pinfunction "O_3") (pintype "passive"))
      (node (ref "S13") (pin "3") (pinfunction "O_3") (pintype "passive"))
      (node (ref "S14") (pin "3") (pinfunction "O_3") (pintype "passive"))
      (node (ref "S2") (pin "1") (pinfunction "1_1") (pintype "passive"))
      (node (ref "S2") (pin "2") (pinfunction "2_2") (pintype "passive"))
      (node (ref "S3") (pin "1") (pinfunction "1_1") (pintype "passive"))
      (node (ref "S3") (pin "2") (pinfunction "2_2") (pintype "passive"))
      (node (ref "S4") (pin "1") (pinfunction "1_1") (pintype "passive"))
      (node (ref "S4") (pin "2") (pinfunction "2_2") (pintype "passive"))
      (node (ref "S5") (pin "1") (pinfunction "1_1") (pintype "passive"))
      (node (ref "S5") (pin "2") (pinfunction "2_2") (pintype "passive"))
      (node (ref "S6") (pin "1") (pinfunction "1_1") (pintype "passive"))
      (node (ref "S6") (pin "2") (pinfunction "2_2") (pintype "passive"))
      (node (ref "S7") (pin "3") (pinfunction "O_3") (pintype "passive"))
      (node (ref "S8") (pin "3") (pinfunction "O_3") (pintype "passive"))
      (node (ref "S9") (pin "3") (pinfunction "O_3") (pintype "passive"))
      (node (ref "U1") (pin "1") (pinfunction "GND_1") (pintype "power_in"))
      (node (ref "U1") (pin "40") (pinfunction "GND_40") (pintype "power_in"))
      (node (ref "U1") (pin "41_1") (pinfunction "GND_41_1") (pintype "power_in"))
      (node (ref "U1") (pin "41_2") (pinfunction "GND_41_2") (pintype "power_in"))
      (node (ref "U1") (pin "41_3") (pinfunction "GND_41_3") (pintype "power_in"))
      (node (ref "U1") (pin "41_4") (pinfunction "GND_41_4") (pintype "power_in"))
      (node (ref "U1") (pin "41_5") (pinfunction "GND_41_5") (pintype "power_in"))
      (node (ref "U1") (pin "41_6") (pinfunction "GND_41_6") (pintype "power_in"))
      (node (ref "U1") (pin "41_7") (pinfunction "GND_41_7") (pintype "power_in"))
      (node (ref "U1") (pin "41_8") (pinfunction "GND_41_8") (pintype "power_in"))
      (node (ref "U1") (pin "41_9") (pinfunction "GND_41_9") (pintype "power_in"))
      (node (ref "X1") (pin "10") (pinfunction "KL_10") (pintype "passive"))
      (node (ref "X2") (pin "10") (pinfunction "KL_10") (pintype "passive"))
      (node (ref "X3") (pin "10") (pinfunction "KL_10") (pintype "passive"))
      (node (ref "X4") (pin "10") (pinfunction "KL_10") (pintype "passive"))
      (node (ref "X5") (pin "10") (pinfunction "KL_10") (pintype "passive"))
    )
    (net (code "13") (name "GPB0") (class "Default")
      (node (ref "IC3") (pin "1") (pinfunction "GPB0_1") (pintype "bidirectional"))
      (node (ref "X1") (pin "1") (pinfunction "KL_1") (pintype "passive"))
    )
    (net (code "14") (name "GPB1") (class "Default")
      (node (ref "IC3") (pin "2") (pinfunction "GPB1_2") (pintype "bidirectional"))
      (node (ref "X1") (pin "2") (pinfunction "KL_2") (pintype "passive"))
    )
    (net (code "15") (name "GPB2") (class "Default")
      (node (ref "IC3") (pin "3") (pinfunction "GPB2_3") (pintype "bidirectional"))
      (node (ref "X1") (pin "3") (pinfunction "KL_3") (pintype "passive"))
    )
    (net (code "16") (name "GPB3") (class "Default")
      (node (ref "IC3") (pin "4") (pinfunction "GPB3_4") (pintype "bidirectional"))
      (node (ref "X1") (pin "4") (pinfunction "KL_4") (pintype "passive"))
    )
    (net (code "17") (name "GPB4") (class "Default")
      (node (ref "IC3") (pin "5") (pinfunction "GPB4_5") (pintype "bidirectional"))
      (node (ref "X1") (pin "5") (pinfunction "KL_5") (pintype "passive"))
    )
    (net (code "18") (name "GPB5") (class "Default")
      (node (ref "IC3") (pin "6") (pinfunction "GPB5_6") (pintype "bidirectional"))
      (node (ref "X1") (pin "6") (pinfunction "KL_6") (pintype "passive"))
    )
    (net (code "19") (name "GPB6") (class "Default")
      (node (ref "IC3") (pin "7") (pinfunction "GPB6_7") (pintype "bidirectional"))
      (node (ref "X1") (pin "7") (pinfunction "KL_7") (pintype "passive"))
    )
    (net (code "20") (name "GPB7") (class "Default")
      (node (ref "IC3") (pin "8") (pinfunction "GPB7_8") (pintype "bidirectional"))
      (node (ref "X1") (pin "8") (pinfunction "KL_8") (pintype "passive"))
    )
    (net (code "21") (name "GPIO4") (class "Default")
      (node (ref "U1") (pin "4") (pinfunction "IO4_4") (pintype "bidirectional"))
      (node (ref "X3") (pin "1") (pinfunction "KL_1") (pintype "passive"))
    )
    (net (code "22") (name "GPIO5") (class "Default")
      (node (ref "U1") (pin "5") (pinfunction "IO5_5") (pintype "bidirectional"))
      (node (ref "X3") (pin "2") (pinfunction "KL_2") (pintype "passive"))
    )
    (net (code "23") (name "GPIO6") (class "Default")
      (node (ref "U1") (pin "6") (pinfunction "IO6_6") (pintype "bidirectional"))
      (node (ref "X3") (pin "3") (pinfunction "KL_3") (pintype "passive"))
    )
    (net (code "24") (name "GPIO7") (class "Default")
      (node (ref "U1") (pin "7") (pinfunction "IO7_7") (pintype "bidirectional"))
      (node (ref "X3") (pin "4") (pinfunction "KL_4") (pintype "passive"))
    )
    (net (code "25") (name "GPIO8") (class "Default")
      (node (ref "U1") (pin "12") (pinfunction "IO8_12") (pintype "bidirectional"))
      (node (ref "X3") (pin "5") (pinfunction "KL_5") (pintype "passive"))
    )
    (net (code "26") (name "GPIO9") (class "Default")
      (node (ref "U1") (pin "17") (pinfunction "IO9_17") (pintype "bidirectional"))
      (node (ref "X3") (pin "6") (pinfunction "KL_6") (pintype "passive"))
    )
    (net (code "27") (name "GPIO10") (class "Default")
      (node (ref "U1") (pin "18") (pinfunction "IO10_18") (pintype "bidirectional"))
      (node (ref "X3") (pin "7") (pinfunction "KL_7") (pintype "passive"))
    )
    (net (code "28") (name "GPIO11") (class "Default")
      (node (ref "U1") (pin "19") (pinfunction "IO11_19") (pintype "bidirectional"))
      (node (ref "X3") (pin "8") (pinfunction "KL_8") (pintype "passive"))
    )
    (net (code "29") (name "GPIO12") (class "Default")
      (node (ref "U1") (pin "20") (pinfunction "IO12_20") (pintype "bidirectional"))
      (node (ref "X4") (pin "1") (pinfunction "KL_1") (pintype "passive"))
    )
    (net (code "30") (name "GPIO13") (class "Default")
      (node (ref "U1") (pin "21") (pinfunction "IO13_21") (pintype "bidirectional"))
      (node (ref "X4") (pin "2") (pinfunction "KL_2") (pintype "passive"))
    )
    (net (code "31") (name "GPIO14") (class "Default")
      (node (ref "U1") (pin "22") (pinfunction "IO14_22") (pintype "bidirectional"))
      (node (ref "X4") (pin "3") (pinfunction "KL_3") (pintype "passive"))
    )
    (net (code "32") (name "GPIO15") (class "Default")
      (node (ref "U1") (pin "8") (pinfunction "IO15_8") (pintype "bidirectional"))
      (node (ref "X4") (pin "4") (pinfunction "KL_4") (pintype "passive"))
    )
    (net (code "33") (name "GPIO16") (class "Default")
      (node (ref "U1") (pin "9") (pinfunction "IO16_9") (pintype "bidirectional"))
      (node (ref "X4") (pin "5") (pinfunction "KL_5") (pintype "passive"))
    )
    (net (code "34") (name "GPIO17") (class "Default")
      (node (ref "U1") (pin "10") (pinfunction "IO17_10") (pintype "bidirectional"))
      (node (ref "X4") (pin "6") (pinfunction "KL_6") (pintype "passive"))
    )
    (net (code "35") (name "GPIO18") (class "Default")
      (node (ref "U1") (pin "11") (pinfunction "IO18_11") (pintype "bidirectional"))
      (node (ref "X4") (pin "7") (pinfunction "KL_7") (pintype "passive"))
    )
    (net (code "36") (name "GPIO48") (class "Default")
      (node (ref "U1") (pin "25") (pinfunction "IO48_25") (pintype "bidirectional"))
      (node (ref "X4") (pin "8") (pinfunction "KL_8") (pintype "passive"))
    )
    (net (code "37") (name "I2C_SCL") (class "Default")
      (node (ref "IC2") (pin "12") (pinfunction "SCL_12") (pintype "bidirectional"))
      (node (ref "IC3") (pin "12") (pinfunction "SCL_12") (pintype "bidirectional"))
      (node (ref "U1") (pin "16") (pinfunction "IO46_16") (pintype "bidirectional"))
      (node (ref "X5") (pin "3") (pinfunction "KL_3") (pintype "passive"))
    )
    (net (code "38") (name "I2C_SDA") (class "Default")
      (node (ref "IC2") (pin "13") (pinfunction "SDA_13") (pintype "bidirectional"))
      (node (ref "IC3") (pin "13") (pinfunction "SDA_13") (pintype "bidirectional"))
      (node (ref "U1") (pin "24") (pinfunction "IO47_24") (pintype "bidirectional"))
      (node (ref "X5") (pin "4") (pinfunction "KL_4") (pintype "passive"))
    )
    (net (code "39") (name "INTA1") (class "Default")
      (node (ref "IC2") (pin "20") (pinfunction "INTA_20") (pintype "bidirectional"))
      (node (ref "JMP2") (pin "3") (pinfunction "3_3") (pintype "passive"))
    )
    (net (code "40") (name "INTA2") (class "Default")
      (node (ref "IC3") (pin "20") (pinfunction "INTA_20") (pintype "bidirectional"))
      (node (ref "JMP2") (pin "1") (pinfunction "1_1") (pintype "passive"))
    )
    (net (code "41") (name "INTB1") (class "Default")
      (node (ref "IC2") (pin "19") (pinfunction "INTB_19") (pintype "bidirectional"))
      (node (ref "JMP3") (pin "3") (pinfunction "3_3") (pintype "passive"))
    )
    (net (code "42") (name "INTB2") (class "Default")
      (node (ref "IC3") (pin "19") (pinfunction "INTB_19") (pintype "bidirectional"))
      (node (ref "JMP3") (pin "1") (pinfunction "1_1") (pintype "passive"))
    )
    (net (code "43") (name "LED0") (class "Default")
      (node (ref "IC2") (pin "21") (pinfunction "GPA0_21") (pintype "bidirectional"))
      (node (ref "Q16") (pin "1") (pinfunction "G_1") (pintype "passive"))
    )
    (net (code "44") (name "LED1") (class "Default")
      (node (ref "IC2") (pin "22") (pinfunction "GPA1_22") (pintype "bidirectional"))
      (node (ref "Q15") (pin "1") (pinfunction "G_1") (pintype "passive"))
    )
    (net (code "45") (name "LED2") (class "Default")
      (node (ref "IC2") (pin "23") (pinfunction "GPA2_23") (pintype "bidirectional"))
      (node (ref "Q14") (pin "1") (pinfunction "G_1") (pintype "passive"))
    )
    (net (code "46") (name "LED3") (class "Default")
      (node (ref "IC2") (pin "24") (pinfunction "GPA3_24") (pintype "bidirectional"))
      (node (ref "Q13") (pin "1") (pinfunction "G_1") (pintype "passive"))
    )
    (net (code "47") (name "LED4") (class "Default")
      (node (ref "IC2") (pin "25") (pinfunction "GPA4_25") (pintype "bidirectional"))
      (node (ref "Q12") (pin "1") (pinfunction "G_1") (pintype "passive"))
    )
    (net (code "48") (name "LED5") (class "Default")
      (node (ref "IC2") (pin "26") (pinfunction "GPA5_26") (pintype "bidirectional"))
      (node (ref "Q11") (pin "1") (pinfunction "G_1") (pintype "passive"))
    )
    (net (code "49") (name "LED6") (class "Default")
      (node (ref "IC2") (pin "27") (pinfunction "GPA6_27") (pintype "bidirectional"))
      (node (ref "Q10") (pin "1") (pinfunction "G_1") (pintype "passive"))
    )
    (net (code "50") (name "LED7") (class "Default")
      (node (ref "IC2") (pin "28") (pinfunction "GPA7_28") (pintype "bidirectional"))
      (node (ref "Q9") (pin "1") (pinfunction "G_1") (pintype "passive"))
    )
    (net (code "51") (name "LED8") (class "Default")
      (node (ref "IC2") (pin "1") (pinfunction "GPB0_1") (pintype "bidirectional"))
      (node (ref "Q8") (pin "1") (pinfunction "G_1") (pintype "passive"))
      (node (ref "X2") (pin "1") (pinfunction "KL_1") (pintype "passive"))
    )
    (net (code "52") (name "LED9") (class "Default")
      (node (ref "IC2") (pin "2") (pinfunction "GPB1_2") (pintype "bidirectional"))
      (node (ref "Q7") (pin "1") (pinfunction "G_1") (pintype "passive"))
      (node (ref "X2") (pin "2") (pinfunction "KL_2") (pintype "passive"))
    )
    (net (code "53") (name "LED10") (class "Default")
      (node (ref "IC2") (pin "3") (pinfunction "GPB2_3") (pintype "bidirectional"))
      (node (ref "Q6") (pin "1") (pinfunction "G_1") (pintype "passive"))
      (node (ref "X2") (pin "3") (pinfunction "KL_3") (pintype "passive"))
    )
    (net (code "54") (name "LED11") (class "Default")
      (node (ref "IC2") (pin "4") (pinfunction "GPB3_4") (pintype "bidirectional"))
      (node (ref "Q5") (pin "1") (pinfunction "G_1") (pintype "passive"))
      (node (ref "X2") (pin "4") (pinfunction "KL_4") (pintype "passive"))
    )
    (net (code "55") (name "LED12") (class "Default")
      (node (ref "IC2") (pin "5") (pinfunction "GPB4_5") (pintype "bidirectional"))
      (node (ref "Q4") (pin "1") (pinfunction "G_1") (pintype "passive"))
      (node (ref "X2") (pin "5") (pinfunction "KL_5") (pintype "passive"))
    )
    (net (code "56") (name "LED13") (class "Default")
      (node (ref "IC2") (pin "6") (pinfunction "GPB5_6") (pintype "bidirectional"))
      (node (ref "Q3") (pin "1") (pinfunction "G_1") (pintype "passive"))
      (node (ref "X2") (pin "6") (pinfunction "KL_6") (pintype "passive"))
    )
    (net (code "57") (name "LED14") (class "Default")
      (node (ref "IC2") (pin "7") (pinfunction "GPB6_7") (pintype "bidirectional"))
      (node (ref "Q2") (pin "1") (pinfunction "G_1") (pintype "passive"))
      (node (ref "X2") (pin "7") (pinfunction "KL_7") (pintype "passive"))
    )
    (net (code "58") (name "LED15") (class "Default")
      (node (ref "IC2") (pin "8") (pinfunction "GPB7_8") (pintype "bidirectional"))
      (node (ref "Q1") (pin "1") (pinfunction "G_1") (pintype "passive"))
      (node (ref "X2") (pin "8") (pinfunction "KL_8") (pintype "passive"))
    )
    (net (code "59") (name "Net-(D4-K1)") (class "Default")
      (node (ref "D4") (pin "1") (pinfunction "K1_1") (pintype "bidirectional"))
      (node (ref "F1") (pin "1") (pinfunction "1_1") (pintype "bidirectional"))
      (node (ref "J1") (pin "A4") (pinfunction "VBUS_1_A4") (pintype "bidirectional"))
      (node (ref "J1") (pin "A9") (pinfunction "VBUS_2_A9") (pintype "bidirectional"))
    )
    (net (code "60") (name "Net-(F1-Pad2)") (class "Default")
      (node (ref "F1") (pin "2") (pinfunction "2_2") (pintype "bidirectional"))
      (node (ref "JP1") (pin "1") (pinfunction "1_1") (pintype "passive"))
    )
    (net (code "61") (name "Net-(F2-Pad1)") (class "Default")
      (node (ref "F2") (pin "1") (pinfunction "1_1") (pintype "bidirectional"))
      (node (ref "JP1") (pin "3") (pinfunction "3_3") (pintype "passive"))
    )
    (net (code "62") (name "Net-(F2-Pad2)") (class "Default")
      (node (ref "F2") (pin "2") (pinfunction "2_2") (pintype "bidirectional"))
      (node (ref "VIN") (pin "MP") (pinfunction "MP_MP") (pintype "passive"))
    )
    (net (code "63") (name "Net-(IC1A-I)") (class "Default")
      (node (ref "C9") (pin "1") (pinfunction "1_1") (pintype "passive"))
      (node (ref "IC1") (pin "13") (pinfunction "I_13") (pintype "input"))
      (node (ref "R10") (pin "1") (pinfunction "1_1") (pintype "passive"))
      (node (ref "S3") (pin "3") (pinfunction "3_3") (pintype "passive"))
      (node (ref "S3") (pin "4") (pinfunction "4_4") (pintype "passive"))
    )
    (net (code "64") (name "Net-(IC1B-I)") (class "Default")
      (node (ref "C10") (pin "1") (pinfunction "1_1") (pintype "passive"))
      (node (ref "IC1") (pin "11") (pinfunction "I_11") (pintype "input"))
      (node (ref "R11") (pin "1") (pinfunction "1_1") (pintype "passive"))
      (node (ref "S4") (pin "3") (pinfunction "3_3") (pintype "passive"))
      (node (ref "S4") (pin "4") (pinfunction "4_4") (pintype "passive"))
    )
    (net (code "65") (name "Net-(IC1C-I)") (class "Default")
      (node (ref "C11") (pin "1") (pinfunction "1_1") (pintype "passive"))
      (node (ref "IC1") (pin "9") (pinfunction "I_9") (pintype "input"))
      (node (ref "R12") (pin "1") (pinfunction "1_1") (pintype "passive"))
      (node (ref "S5") (pin "3") (pinfunction "3_3") (pintype "passive"))
      (node (ref "S5") (pin "4") (pinfunction "4_4") (pintype "passive"))
    )
    (net (code "66") (name "Net-(IC1D-I)") (class "Default")
      (node (ref "C12") (pin "1") (pinfunction "1_1") (pintype "passive"))
      (node (ref "IC1") (pin "1") (pinfunction "I_1") (pintype "input"))
      (node (ref "R13") (pin "1") (pinfunction "1_1") (pintype "passive"))
      (node (ref "S6") (pin "3") (pinfunction "3_3") (pintype "passive"))
      (node (ref "S6") (pin "4") (pinfunction "4_4") (pintype "passive"))
    )
    (net (code "67") (name "Net-(JMP1-Pad2)") (class "Default")
      (node (ref "JMP1") (pin "2") (pinfunction "2_2") (pintype "passive"))
      (node (ref "R7") (pin "1") (pinfunction "1_1") (pintype "passive"))
    )
    (net (code "68") (name "Net-(LED1-PadA)") (class "Default")
      (node (ref "LED1") (pin "A") (pinfunction "A_A") (pintype "passive"))
      (node (ref "R3") (pin "1") (pinfunction "1_1") (pintype "passive"))
    )
    (net (code "69") (name "Net-(LED2-PadA)") (class "Default")
      (node (ref "LED2") (pin "A") (pinfunction "A_A") (pintype "passive"))
      (node (ref "R4") (pin "1") (pinfunction "1_1") (pintype "passive"))
    )
    (net (code "70") (name "Net-(LED3-DO)") (class "Default")
      (node (ref "LED3") (pin "1") (pinfunction "DO_1") (pintype "bidirectional"))
      (node (ref "LED4") (pin "3") (pinfunction "DI_3") (pintype "bidirectional"))
    )
    (net (code "71") (name "Net-(LED7-PadA)") (class "Default")
      (node (ref "LED7") (pin "A") (pinfunction "A_A") (pintype "passive"))
      (node (ref "R14") (pin "1") (pinfunction "1_1") (pintype "passive"))
    )
    (net (code "72") (name "Net-(LED8-PadA)") (class "Default")
      (node (ref "LED8") (pin "A") (pinfunction "A_A") (pintype "passive"))
      (node (ref "R15") (pin "1") (pinfunction "1_1") (pintype "passive"))
    )
    (net (code "73") (name "Net-(LED9-PadA)") (class "Default")
      (node (ref "LED9") (pin "A") (pinfunction "A_A") (pintype "passive"))
      (node (ref "R16") (pin "1") (pinfunction "1_1") (pintype "passive"))
    )
    (net (code "74") (name "Net-(LED10-PadA)") (class "Default")
      (node (ref "LED10") (pin "A") (pinfunction "A_A") (pintype "passive"))
      (node (ref "R17") (pin "1") (pinfunction "1_1") (pintype "passive"))
    )
    (net (code "75") (name "Net-(LED11-PadA)") (class "Default")
      (node (ref "LED11") (pin "A") (pinfunction "A_A") (pintype "passive"))
      (node (ref "R18") (pin "1") (pinfunction "1_1") (pintype "passive"))
    )
    (net (code "76") (name "Net-(LED12-PadA)") (class "Default")
      (node (ref "LED12") (pin "A") (pinfunction "A_A") (pintype "passive"))
      (node (ref "R19") (pin "1") (pinfunction "1_1") (pintype "passive"))
    )
    (net (code "77") (name "Net-(LED13-PadA)") (class "Default")
      (node (ref "LED13") (pin "A") (pinfunction "A_A") (pintype "passive"))
      (node (ref "R20") (pin "1") (pinfunction "1_1") (pintype "passive"))
    )
    (net (code "78") (name "Net-(LED14-PadA)") (class "Default")
      (node (ref "LED14") (pin "A") (pinfunction "A_A") (pintype "passive"))
      (node (ref "R21") (pin "1") (pinfunction "1_1") (pintype "passive"))
    )
    (net (code "79") (name "Net-(LED15-PadA)") (class "Default")
      (node (ref "LED15") (pin "A") (pinfunction "A_A") (pintype "passive"))
      (node (ref "R22") (pin "1") (pinfunction "1_1") (pintype "passive"))
    )
    (net (code "80") (name "Net-(LED16-PadA)") (class "Default")
      (node (ref "LED16") (pin "A") (pinfunction "A_A") (pintype "passive"))
      (node (ref "R23") (pin "1") (pinfunction "1_1") (pintype "passive"))
    )
    (net (code "81") (name "Net-(LED17-PadA)") (class "Default")
      (node (ref "LED17") (pin "A") (pinfunction "A_A") (pintype "passive"))
      (node (ref "R24") (pin "1") (pinfunction "1_1") (pintype "passive"))
    )
    (net (code "82") (name "Net-(LED18-PadA)") (class "Default")
      (node (ref "LED18") (pin "A") (pinfunction "A_A") (pintype "passive"))
      (node (ref "R25") (pin "1") (pinfunction "1_1") (pintype "passive"))
    )
    (net (code "83") (name "Net-(LED19-PadA)") (class "Default")
      (node (ref "LED19") (pin "A") (pinfunction "A_A") (pintype "passive"))
      (node (ref "R26") (pin "1") (pinfunction "1_1") (pintype "passive"))
    )
    (net (code "84") (name "Net-(LED20-PadA)") (class "Default")
      (node (ref "LED20") (pin "A") (pinfunction "A_A") (pintype "passive"))
      (node (ref "R27") (pin "1") (pinfunction "1_1") (pintype "passive"))
    )
    (net (code "85") (name "Net-(LED21-PadA)") (class "Default")
      (node (ref "LED21") (pin "A") (pinfunction "A_A") (pintype "passive"))
      (node (ref "R28") (pin "1") (pinfunction "1_1") (pintype "passive"))
    )
    (net (code "86") (name "Net-(LED22-PadA)") (class "Default")
      (node (ref "LED22") (pin "A") (pinfunction "A_A") (pintype "passive"))
      (node (ref "R29") (pin "1") (pinfunction "1_1") (pintype "passive"))
    )
    (net (code "87") (name "Net-(Q1-D)") (class "Default")
      (node (ref "LED7") (pin "C") (pinfunction "C_C") (pintype "passive"))
      (node (ref "Q1") (pin "3") (pinfunction "D_3") (pintype "passive"))
    )
    (net (code "88") (name "Net-(Q2-D)") (class "Default")
      (node (ref "LED8") (pin "C") (pinfunction "C_C") (pintype "passive"))
      (node (ref "Q2") (pin "3") (pinfunction "D_3") (pintype "passive"))
    )
    (net (code "89") (name "Net-(Q3-D)") (class "Default")
      (node (ref "LED9") (pin "C") (pinfunction "C_C") (pintype "passive"))
      (node (ref "Q3") (pin "3") (pinfunction "D_3") (pintype "passive"))
    )
    (net (code "90") (name "Net-(Q4-D)") (class "Default")
      (node (ref "LED10") (pin "C") (pinfunction "C_C") (pintype "passive"))
      (node (ref "Q4") (pin "3") (pinfunction "D_3") (pintype "passive"))
    )
    (net (code "91") (name "Net-(Q5-D)") (class "Default")
      (node (ref "LED11") (pin "C") (pinfunction "C_C") (pintype "passive"))
      (node (ref "Q5") (pin "3") (pinfunction "D_3") (pintype "passive"))
    )
    (net (code "92") (name "Net-(Q6-D)") (class "Default")
      (node (ref "LED12") (pin "C") (pinfunction "C_C") (pintype "passive"))
      (node (ref "Q6") (pin "3") (pinfunction "D_3") (pintype "passive"))
    )
    (net (code "93") (name "Net-(Q7-D)") (class "Default")
      (node (ref "LED13") (pin "C") (pinfunction "C_C") (pintype "passive"))
      (node (ref "Q7") (pin "3") (pinfunction "D_3") (pintype "passive"))
    )
    (net (code "94") (name "Net-(Q8-D)") (class "Default")
      (node (ref "LED14") (pin "C") (pinfunction "C_C") (pintype "passive"))
      (node (ref "Q8") (pin "3") (pinfunction "D_3") (pintype "passive"))
    )
    (net (code "95") (name "Net-(Q9-D)") (class "Default")
      (node (ref "LED15") (pin "C") (pinfunction "C_C") (pintype "passive"))
      (node (ref "Q9") (pin "3") (pinfunction "D_3") (pintype "passive"))
    )
    (net (code "96") (name "Net-(Q10-D)") (class "Default")
      (node (ref "LED16") (pin "C") (pinfunction "C_C") (pintype "passive"))
      (node (ref "Q10") (pin "3") (pinfunction "D_3") (pintype "passive"))
    )
    (net (code "97") (name "Net-(Q11-D)") (class "Default")
      (node (ref "LED17") (pin "C") (pinfunction "C_C") (pintype "passive"))
      (node (ref "Q11") (pin "3") (pinfunction "D_3") (pintype "passive"))
    )
    (net (code "98") (name "Net-(Q12-D)") (class "Default")
      (node (ref "LED18") (pin "C") (pinfunction "C_C") (pintype "passive"))
      (node (ref "Q12") (pin "3") (pinfunction "D_3") (pintype "passive"))
    )
    (net (code "99") (name "Net-(Q13-D)") (class "Default")
      (node (ref "LED19") (pin "C") (pinfunction "C_C") (pintype "passive"))
      (node (ref "Q13") (pin "3") (pinfunction "D_3") (pintype "passive"))
    )
    (net (code "100") (name "Net-(Q14-D)") (class "Default")
      (node (ref "LED20") (pin "C") (pinfunction "C_C") (pintype "passive"))
      (node (ref "Q14") (pin "3") (pinfunction "D_3") (pintype "passive"))
    )
    (net (code "101") (name "Net-(Q15-D)") (class "Default")
      (node (ref "LED21") (pin "C") (pinfunction "C_C") (pintype "passive"))
      (node (ref "Q15") (pin "3") (pinfunction "D_3") (pintype "passive"))
    )
    (net (code "102") (name "Net-(Q16-D)") (class "Default")
      (node (ref "LED22") (pin "C") (pinfunction "C_C") (pintype "passive"))
      (node (ref "Q16") (pin "3") (pinfunction "D_3") (pintype "passive"))
    )
    (net (code "103") (name "Net-(X5G-KL)") (class "Default")
      (node (ref "JMP2") (pin "2") (pinfunction "2_2") (pintype "passive"))
      (node (ref "X5") (pin "6") (pinfunction "KL_6") (pintype "passive"))
    )
    (net (code "104") (name "Net-(X5H-KL)") (class "Default")
      (node (ref "JMP3") (pin "2") (pinfunction "2_2") (pintype "passive"))
      (node (ref "X5") (pin "7") (pinfunction "KL_7") (pintype "passive"))
    )
    (net (code "105") (name "POT0") (class "Default")
      (node (ref "R8") (pin "2") (pinfunction "S_2") (pintype "passive"))
      (node (ref "U1") (pin "39") (pinfunction "IO1_39") (pintype "bidirectional"))
    )
    (net (code "106") (name "POT1") (class "Default")
      (node (ref "R9") (pin "2") (pinfunction "S_2") (pintype "passive"))
      (node (ref "U1") (pin "38") (pinfunction "IO2_38") (pintype "bidirectional"))
    )
    (net (code "107") (name "RX") (class "Default")
      (node (ref "RX") (pin "MP") (pinfunction "MP_MP") (pintype "passive"))
      (node (ref "U1") (pin "36") (pinfunction "RXD0_36") (pintype "bidirectional"))
      (node (ref "X5") (pin "1") (pinfunction "KL_1") (pintype "passive"))
    )
    (net (code "108") (name "SW") (class "Default")
      (node (ref "C1") (pin "2") (pinfunction "2_2") (pintype "passive"))
      (node (ref "L1") (pin "1") (pinfunction "1_1") (pintype "bidirectional"))
      (node (ref "PS1") (pin "5") (pinfunction "SW_5") (pintype "output"))
    )
    (net (code "109") (name "SW0") (class "Default")
      (node (ref "IC3") (pin "21") (pinfunction "GPA0_21") (pintype "bidirectional"))
      (node (ref "S14") (pin "2") (pinfunction "P_2") (pintype "passive"))
    )
    (net (code "110") (name "SW1") (class "Default")
      (node (ref "IC3") (pin "22") (pinfunction "GPA1_22") (pintype "bidirectional"))
      (node (ref "S13") (pin "2") (pinfunction "P_2") (pintype "passive"))
    )
    (net (code "111") (name "SW2") (class "Default")
      (node (ref "IC3") (pin "23") (pinfunction "GPA2_23") (pintype "bidirectional"))
      (node (ref "S12") (pin "2") (pinfunction "P_2") (pintype "passive"))
    )
    (net (code "112") (name "SW3") (class "Default")
      (node (ref "IC3") (pin "24") (pinfunction "GPA3_24") (pintype "bidirectional"))
      (node (ref "S11") (pin "2") (pinfunction "P_2") (pintype "passive"))
    )
    (net (code "113") (name "SW4") (class "Default")
      (node (ref "IC3") (pin "25") (pinfunction "GPA4_25") (pintype "bidirectional"))
      (node (ref "S10") (pin "2") (pinfunction "P_2") (pintype "passive"))
    )
    (net (code "114") (name "SW5") (class "Default")
      (node (ref "IC3") (pin "26") (pinfunction "GPA5_26") (pintype "bidirectional"))
      (node (ref "S9") (pin "2") (pinfunction "P_2") (pintype "passive"))
    )
    (net (code "115") (name "SW6") (class "Default")
      (node (ref "IC3") (pin "27") (pinfunction "GPA6_27") (pintype "bidirectional"))
      (node (ref "S8") (pin "2") (pinfunction "P_2") (pintype "passive"))
    )
    (net (code "116") (name "SW7") (class "Default")
      (node (ref "IC3") (pin "28") (pinfunction "GPA7_28") (pintype "bidirectional"))
      (node (ref "S7") (pin "2") (pinfunction "P_2") (pintype "passive"))
    )
    (net (code "117") (name "TCK") (class "Default")
      (node (ref "J2") (pin "4") (pinfunction "4_4") (pintype "passive"))
      (node (ref "U1") (pin "32") (pinfunction "IO39_32") (pintype "bidirectional"))
    )
    (net (code "118") (name "TDI") (class "Default")
      (node (ref "J2") (pin "8") (pinfunction "8_8") (pintype "passive"))
      (node (ref "U1") (pin "34") (pinfunction "IO41_34") (pintype "bidirectional"))
    )
    (net (code "119") (name "TDO") (class "Default")
      (node (ref "J2") (pin "6") (pinfunction "6_6") (pintype "passive"))
      (node (ref "U1") (pin "33") (pinfunction "IO40_33") (pintype "bidirectional"))
    )
    (net (code "120") (name "TMS") (class "Default")
      (node (ref "J2") (pin "2") (pinfunction "2_2") (pintype "passive"))
      (node (ref "U1") (pin "35") (pinfunction "IO42_35") (pintype "bidirectional"))
    )
    (net (code "121") (name "TX") (class "Default")
      (node (ref "TX") (pin "MP") (pinfunction "MP_MP") (pintype "passive"))
      (node (ref "U1") (pin "37") (pinfunction "TXD0_37") (pintype "bidirectional"))
      (node (ref "X5") (pin "2") (pinfunction "KL_2") (pintype "passive"))
    )
    (net (code "122") (name "USB_D_N") (class "Default")
      (node (ref "D3") (pin "1") (pinfunction "K1_1") (pintype "bidirectional"))
      (node (ref "J1") (pin "A7") (pinfunction "DN1_A7") (pintype "bidirectional"))
      (node (ref "J1") (pin "B7") (pinfunction "DN2_B7") (pintype "bidirectional"))
      (node (ref "U1") (pin "13") (pinfunction "IO19_13") (pintype "bidirectional"))
    )
    (net (code "123") (name "USB_D_P") (class "Default")
      (node (ref "D2") (pin "1") (pinfunction "K1_1") (pintype "bidirectional"))
      (node (ref "J1") (pin "A6") (pinfunction "DP1_A6") (pintype "bidirectional"))
      (node (ref "J1") (pin "B6") (pinfunction "DP2_B6") (pintype "bidirectional"))
      (node (ref "U1") (pin "14") (pinfunction "IO20_14") (pintype "bidirectional"))
    )
    (net (code "124") (name "VDD_SPI") (class "Default")
      (node (ref "R6") (pin "2") (pinfunction "2_2") (pintype "passive"))
      (node (ref "U1") (pin "26") (pinfunction "IO45_26") (pintype "bidirectional"))
    )
    (net (code "125") (name "VTERMINAL") (class "Default")
      (node (ref "C4") (pin "1") (pinfunction "1_1") (pintype "passive"))
      (node (ref "JP1") (pin "2") (pinfunction "2_2") (pintype "passive"))
      (node (ref "PS1") (pin "2") (pinfunction "EN_2") (pintype "input"))
      (node (ref "PS1") (pin "3") (pinfunction "VIN_3") (pintype "power_in"))
      (node (ref "R4") (pin "2") (pinfunction "2_2") (pintype "passive"))
      (node (ref "X5") (pin "8") (pinfunction "KL_8") (pintype "passive"))
    )
    (net (code "126") (name "WS2812_IN") (class "Default")
      (node (ref "LED3") (pin "3") (pinfunction "DI_3") (pintype "bidirectional"))
      (node (ref "U1") (pin "31") (pinfunction "IO38_31") (pintype "bidirectional"))
    )
    (net (code "127") (name "WS2812_OUT") (class "Default")
      (node (ref "LED4") (pin "1") (pinfunction "DO_1") (pintype "bidirectional"))
      (node (ref "X5") (pin "5") (pinfunction "KL_5") (pintype "passive"))
    )
    (net (code "128") (name "unconnected-(H1-MOUNT-PadB3,3)") (class "Default")
      (node (ref "H1") (pin "B3,3") (pinfunction "MOUNT_B3,3") (pintype "passive"))
    )
    (net (code "129") (name "unconnected-(H2-MOUNT-PadB3,3)") (class "Default")
      (node (ref "H2") (pin "B3,3") (pinfunction "MOUNT_B3,3") (pintype "passive"))
    )
    (net (code "130") (name "unconnected-(H3-MOUNT-PadB3,3)") (class "Default")
      (node (ref "H3") (pin "B3,3") (pinfunction "MOUNT_B3,3") (pintype "passive"))
    )
    (net (code "131") (name "unconnected-(H4-MOUNT-PadB3,3)") (class "Default")
      (node (ref "H4") (pin "B3,3") (pinfunction "MOUNT_B3,3") (pintype "passive"))
    )
    (net (code "132") (name "unconnected-(IC1E-O-Pad4)") (class "Default")
      (node (ref "IC1") (pin "4") (pinfunction "O_4") (pintype "output"))
    )
    (net (code "133") (name "unconnected-(IC1F-O-Pad6)") (class "Default")
      (node (ref "IC1") (pin "6") (pinfunction "O_6") (pintype "output"))
    )
    (net (code "134") (name "unconnected-(IC2-NC_1-Pad11)") (class "Default")
      (node (ref "IC2") (pin "11") (pinfunction "NC_1_11") (pintype "bidirectional"))
    )
    (net (code "135") (name "unconnected-(IC2-NC_2-Pad14)") (class "Default")
      (node (ref "IC2") (pin "14") (pinfunction "NC_2_14") (pintype "bidirectional"))
    )
    (net (code "136") (name "unconnected-(IC3-NC_1-Pad11)") (class "Default")
      (node (ref "IC3") (pin "11") (pinfunction "NC_1_11") (pintype "bidirectional"))
    )
    (net (code "137") (name "unconnected-(IC3-NC_2-Pad14)") (class "Default")
      (node (ref "IC3") (pin "14") (pinfunction "NC_2_14") (pintype "bidirectional"))
    )
    (net (code "138") (name "unconnected-(J1-SBU1-PadA8)") (class "Default")
      (node (ref "J1") (pin "A8") (pinfunction "SBU1_A8") (pintype "bidirectional"))
    )
    (net (code "139") (name "unconnected-(J1-SBU2-PadB8)") (class "Default")
      (node (ref "J1") (pin "B8") (pinfunction "SBU2_B8") (pintype "bidirectional"))
    )
    (net (code "140") (name "unconnected-(J2-Pad10)") (class "Default")
      (node (ref "J2") (pin "10") (pinfunction "10_10") (pintype "passive"))
    )
    (net (code "141") (name "unconnected-(R8-P$1-PadM1)") (class "Default")
      (node (ref "R8") (pin "M1") (pinfunction "P$1_M1") (pintype "bidirectional"))
    )
    (net (code "142") (name "unconnected-(R8-P$2-PadM2)") (class "Default")
      (node (ref "R8") (pin "M2") (pinfunction "P$2_M2") (pintype "bidirectional"))
    )
    (net (code "143") (name "unconnected-(R9-P$1-PadM1)") (class "Default")
      (node (ref "R9") (pin "M1") (pinfunction "P$1_M1") (pintype "bidirectional"))
    )
    (net (code "144") (name "unconnected-(R9-P$2-PadM2)") (class "Default")
      (node (ref "R9") (pin "M2") (pinfunction "P$2_M2") (pintype "bidirectional"))
    )
  )
)
